# TeensySensor.net
KiCad netlist of a schematic drawn in EasyEDA Pro
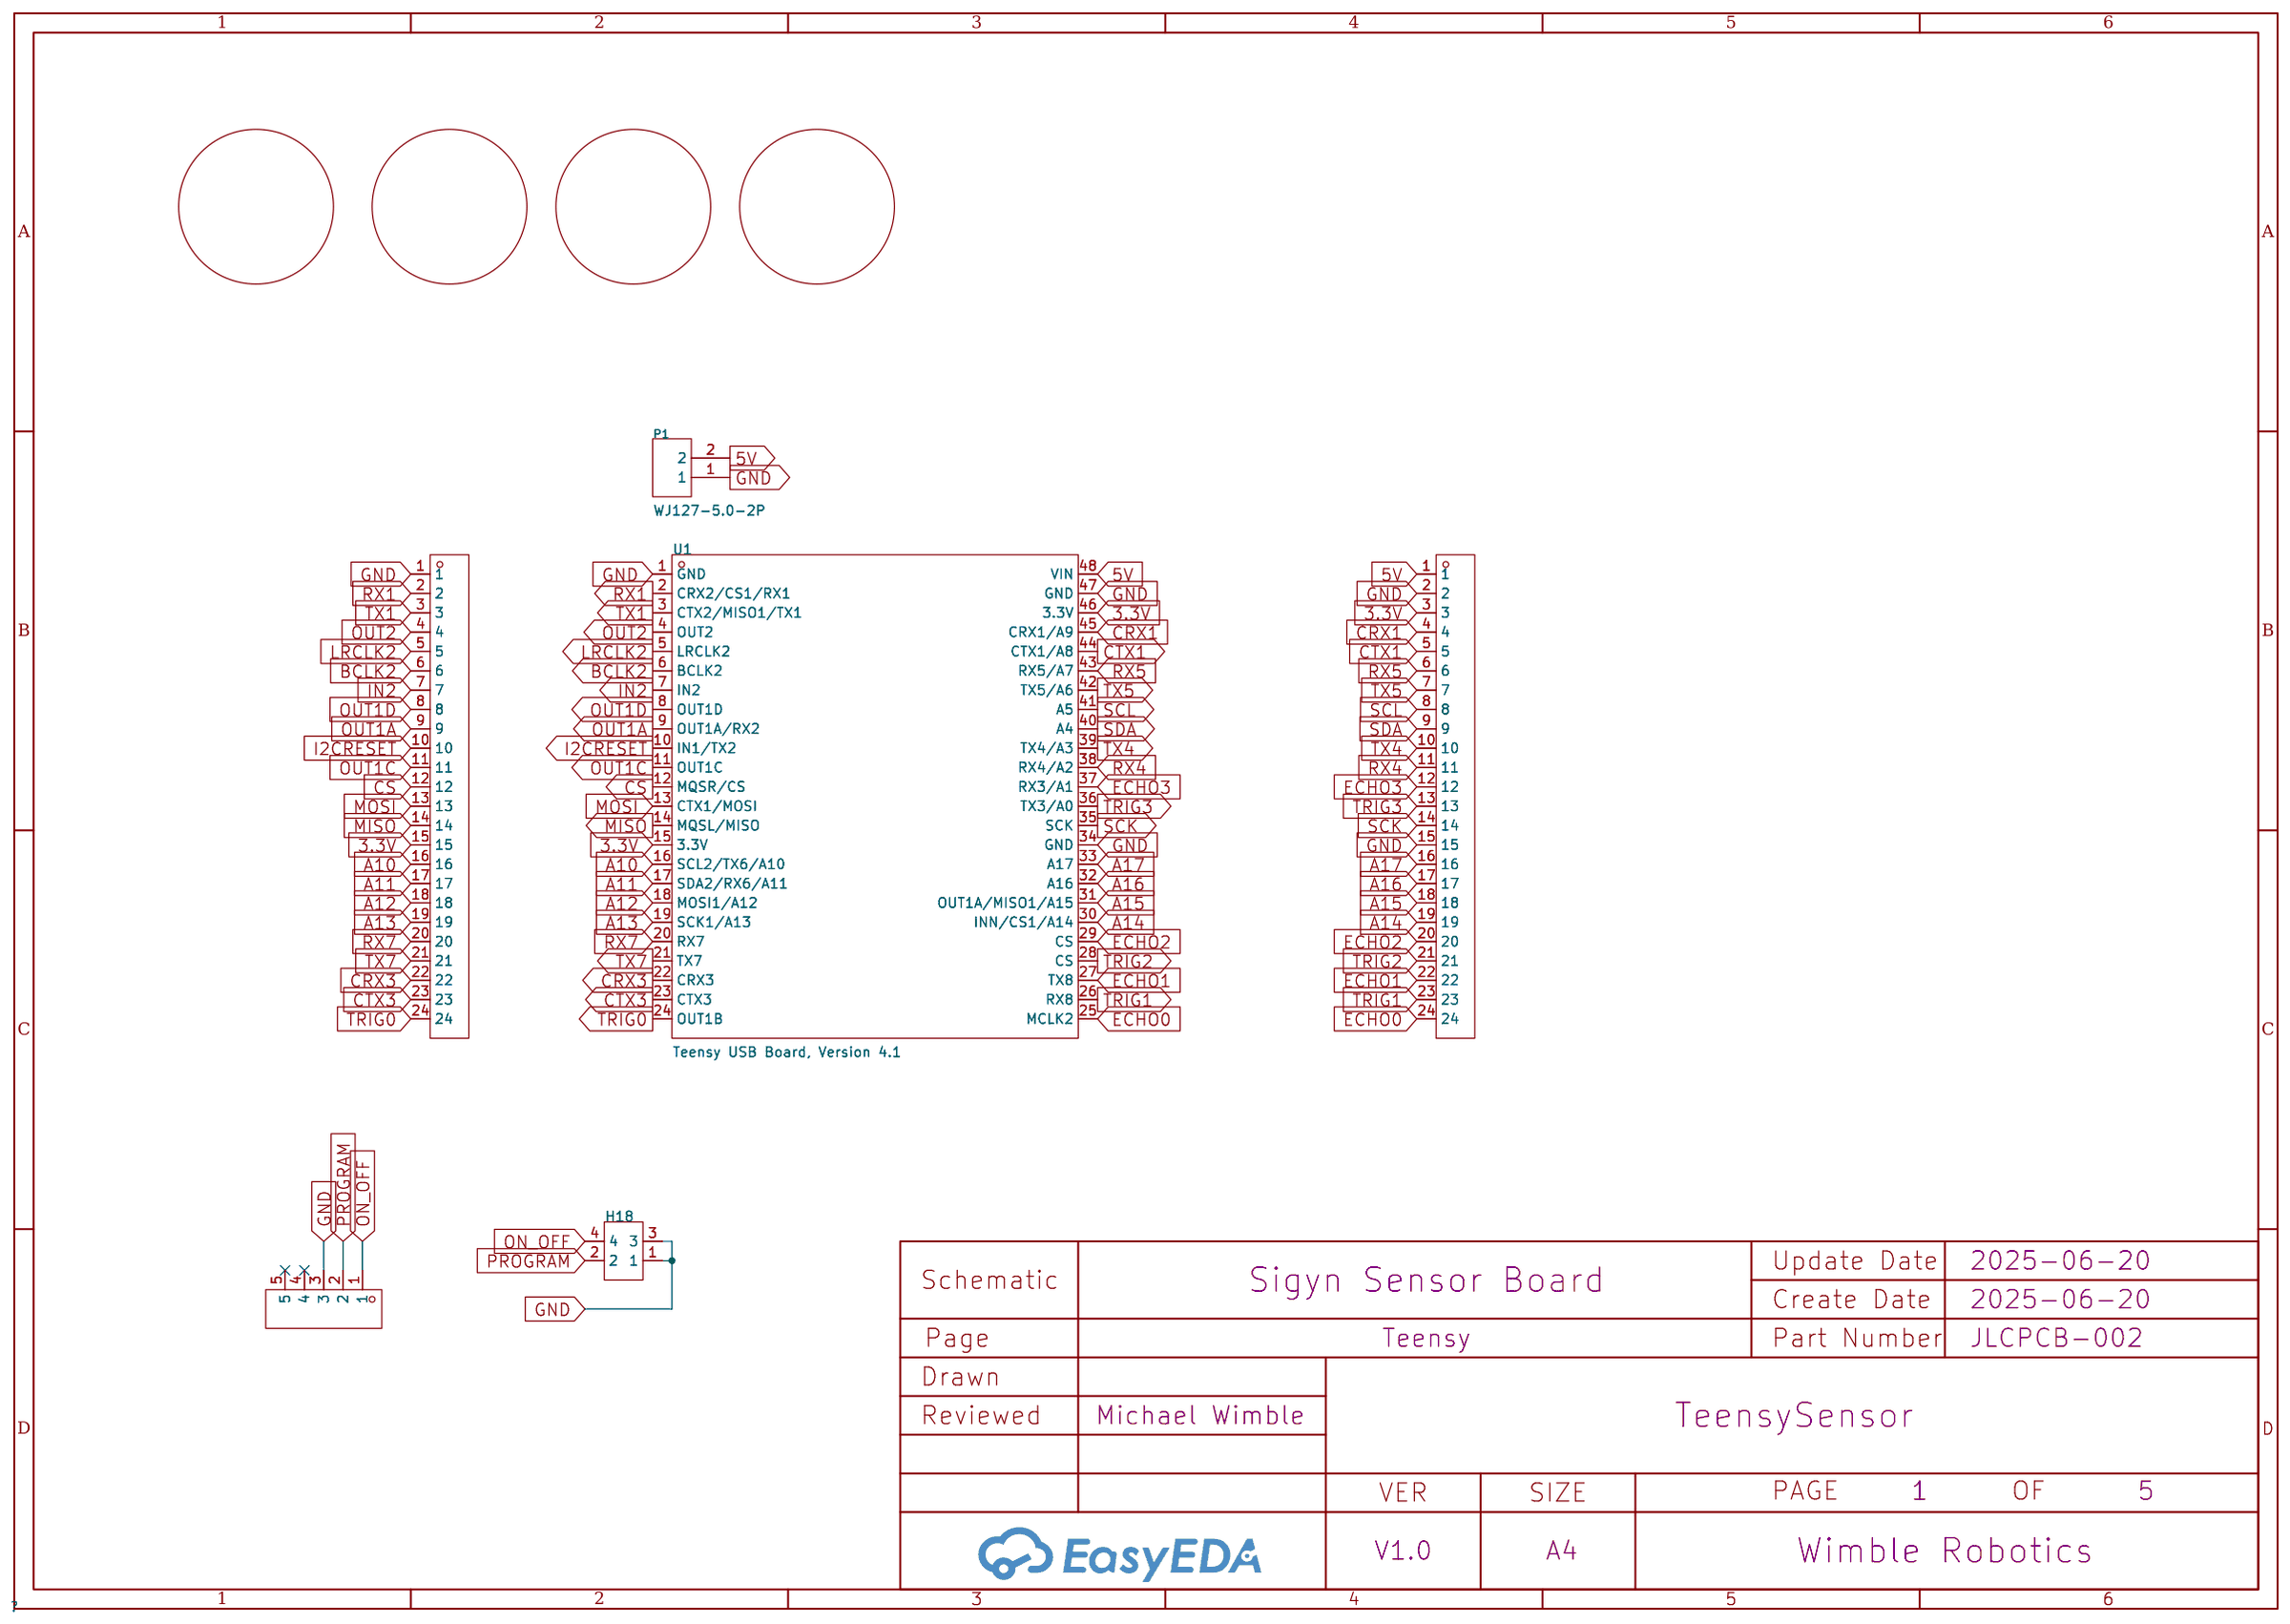
[diagram p0: Teensy]
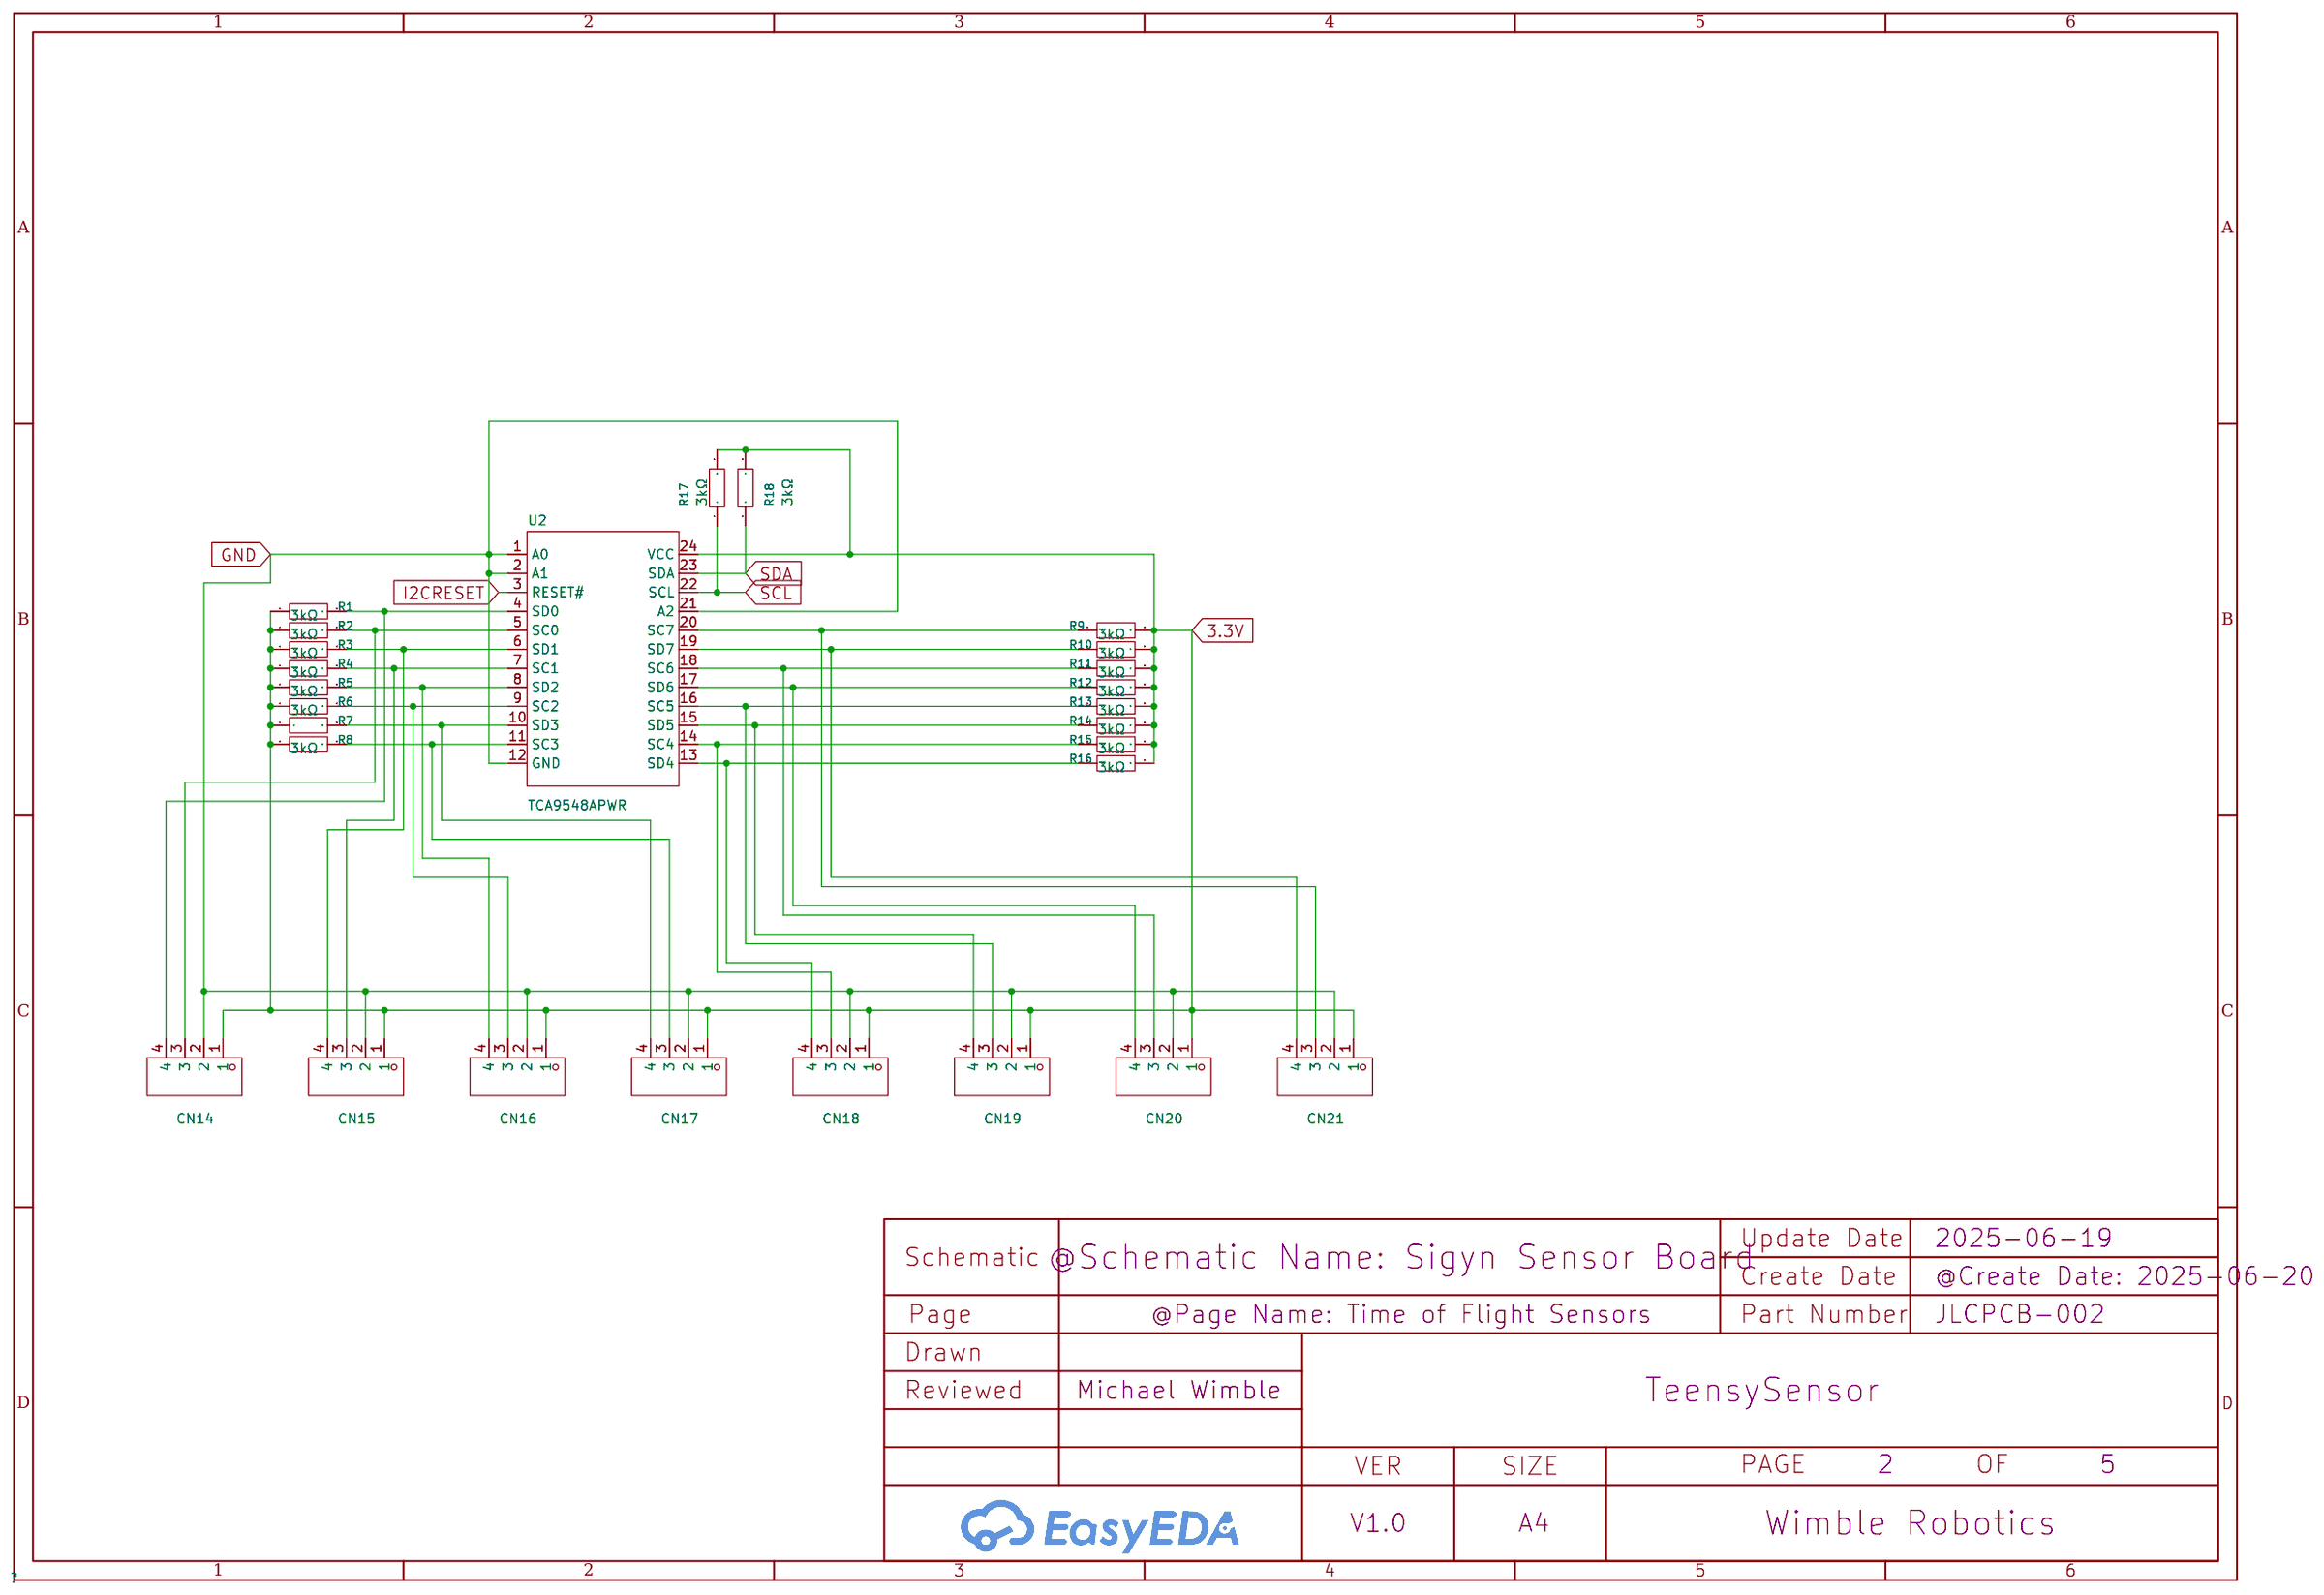
[diagram p1: Time of Flight Sensors]
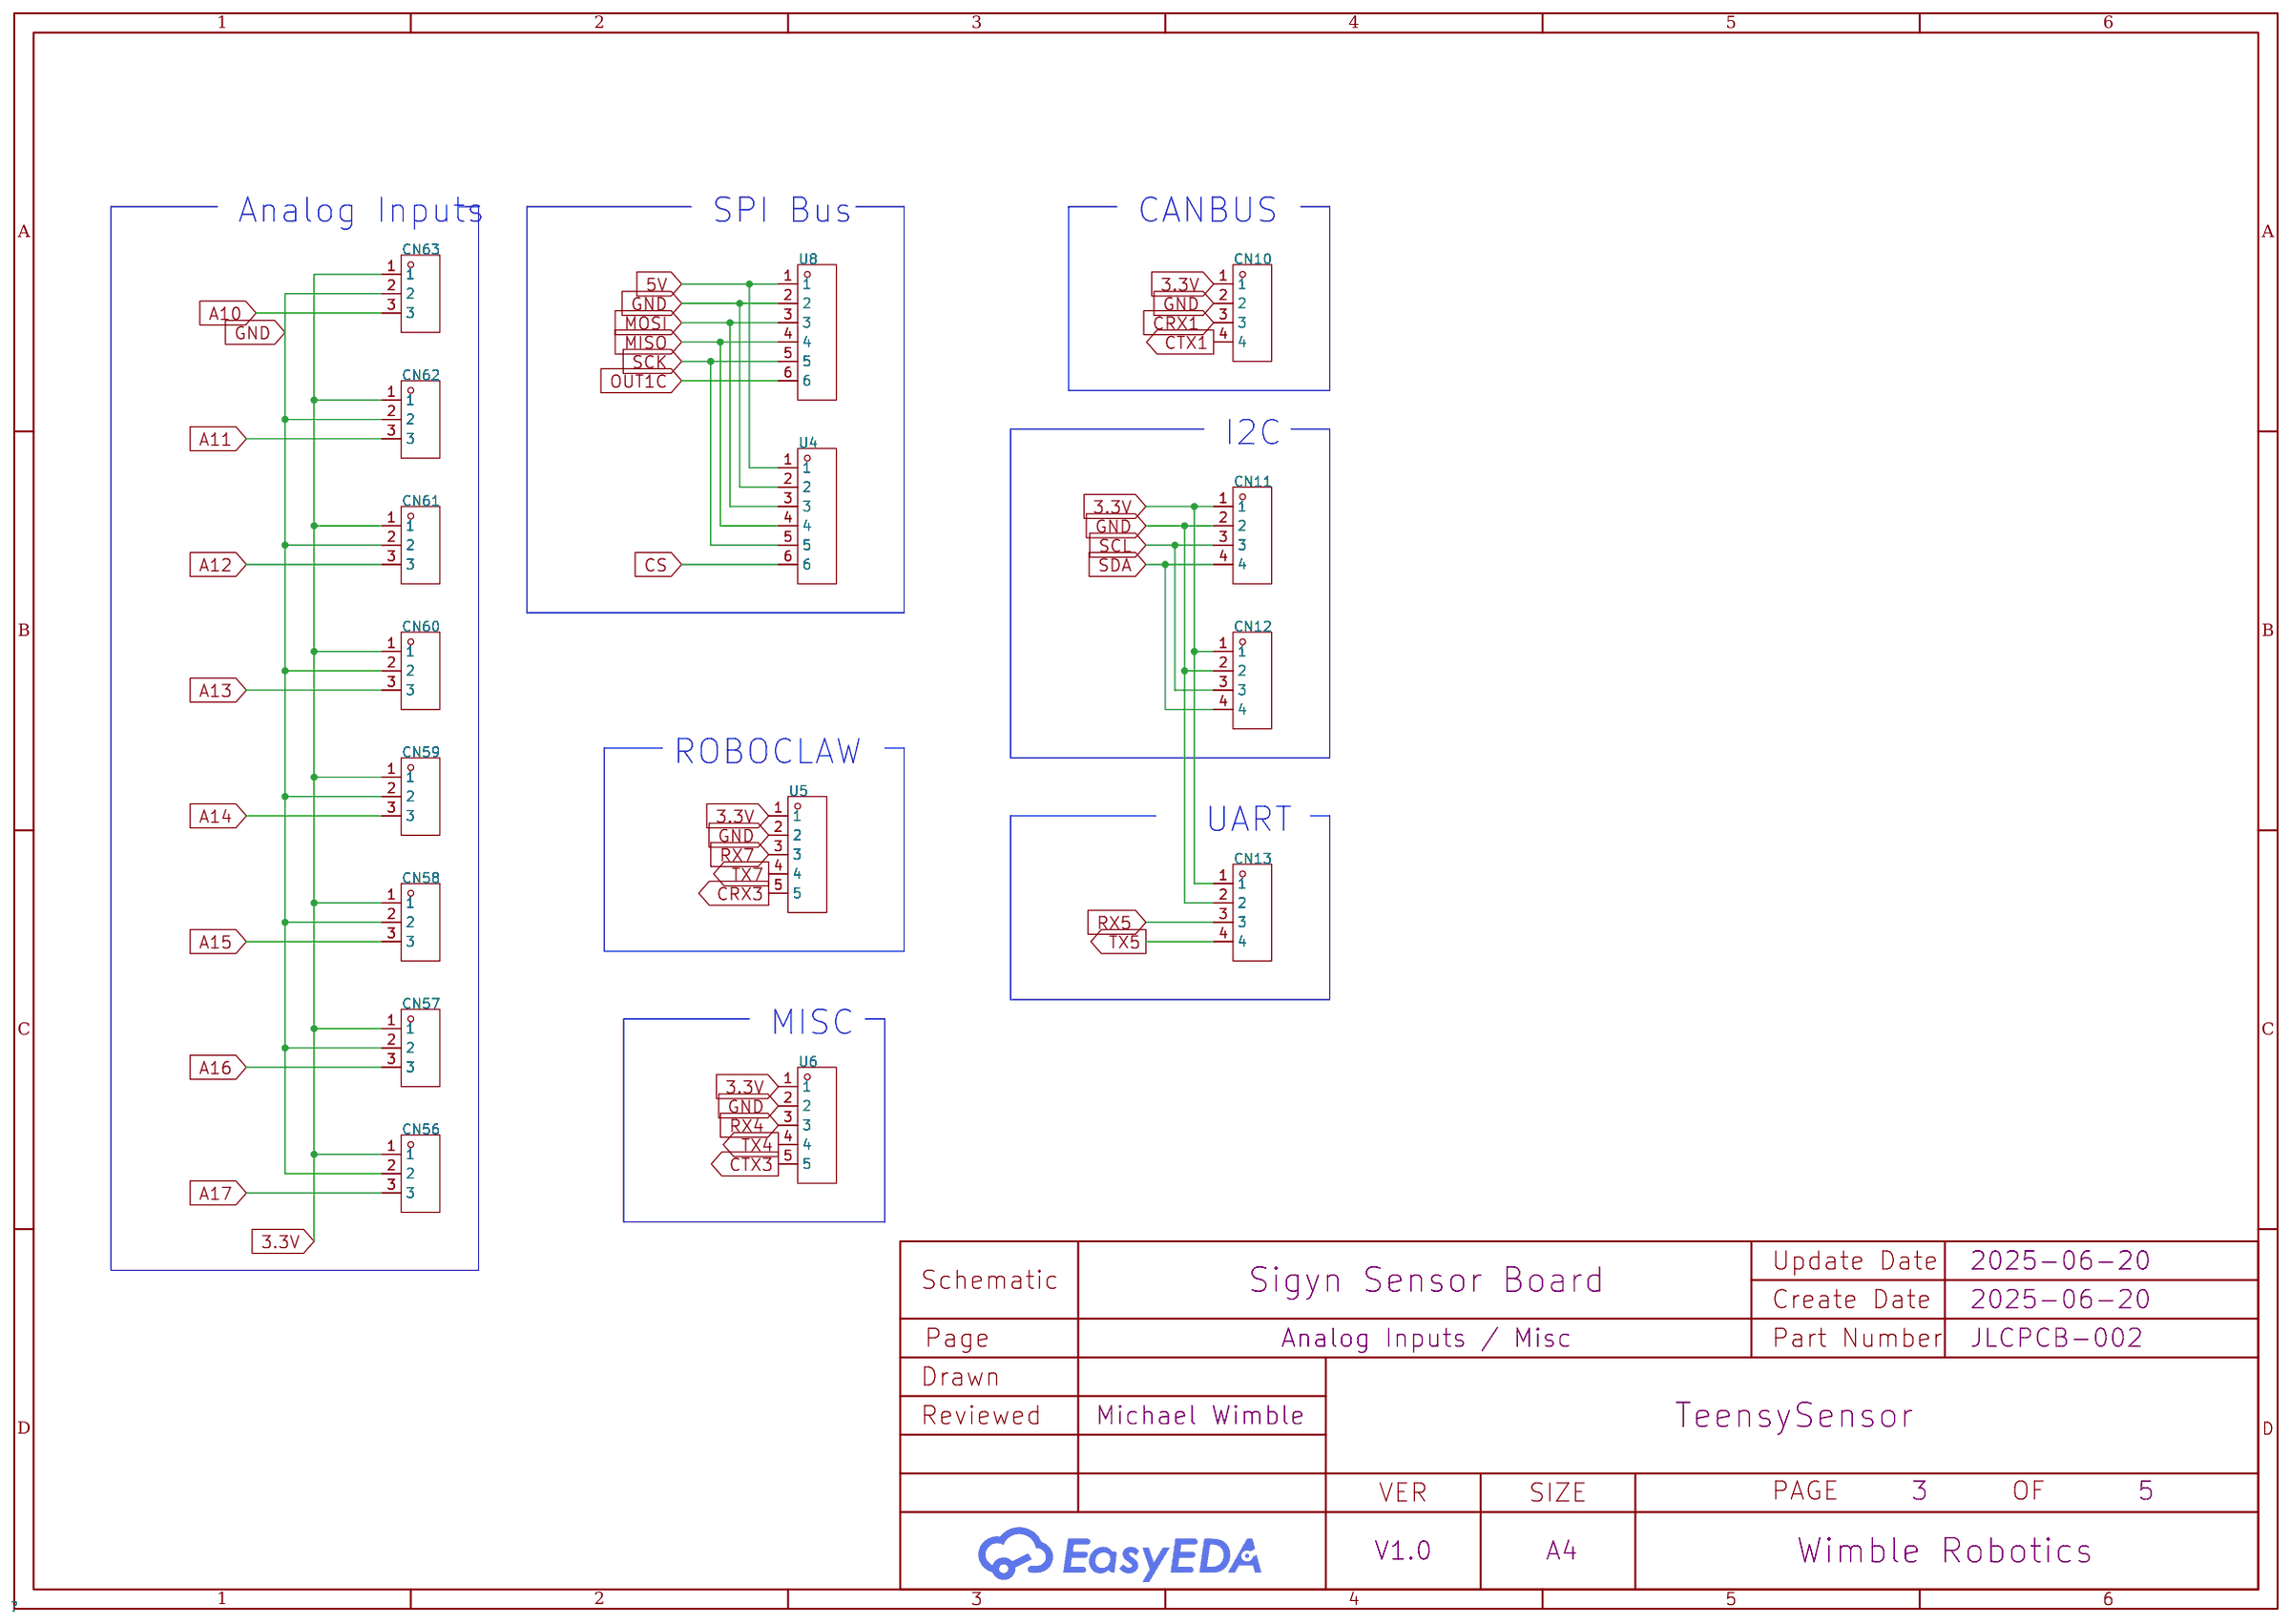
[diagram p2: Analog Inputs / Misc]
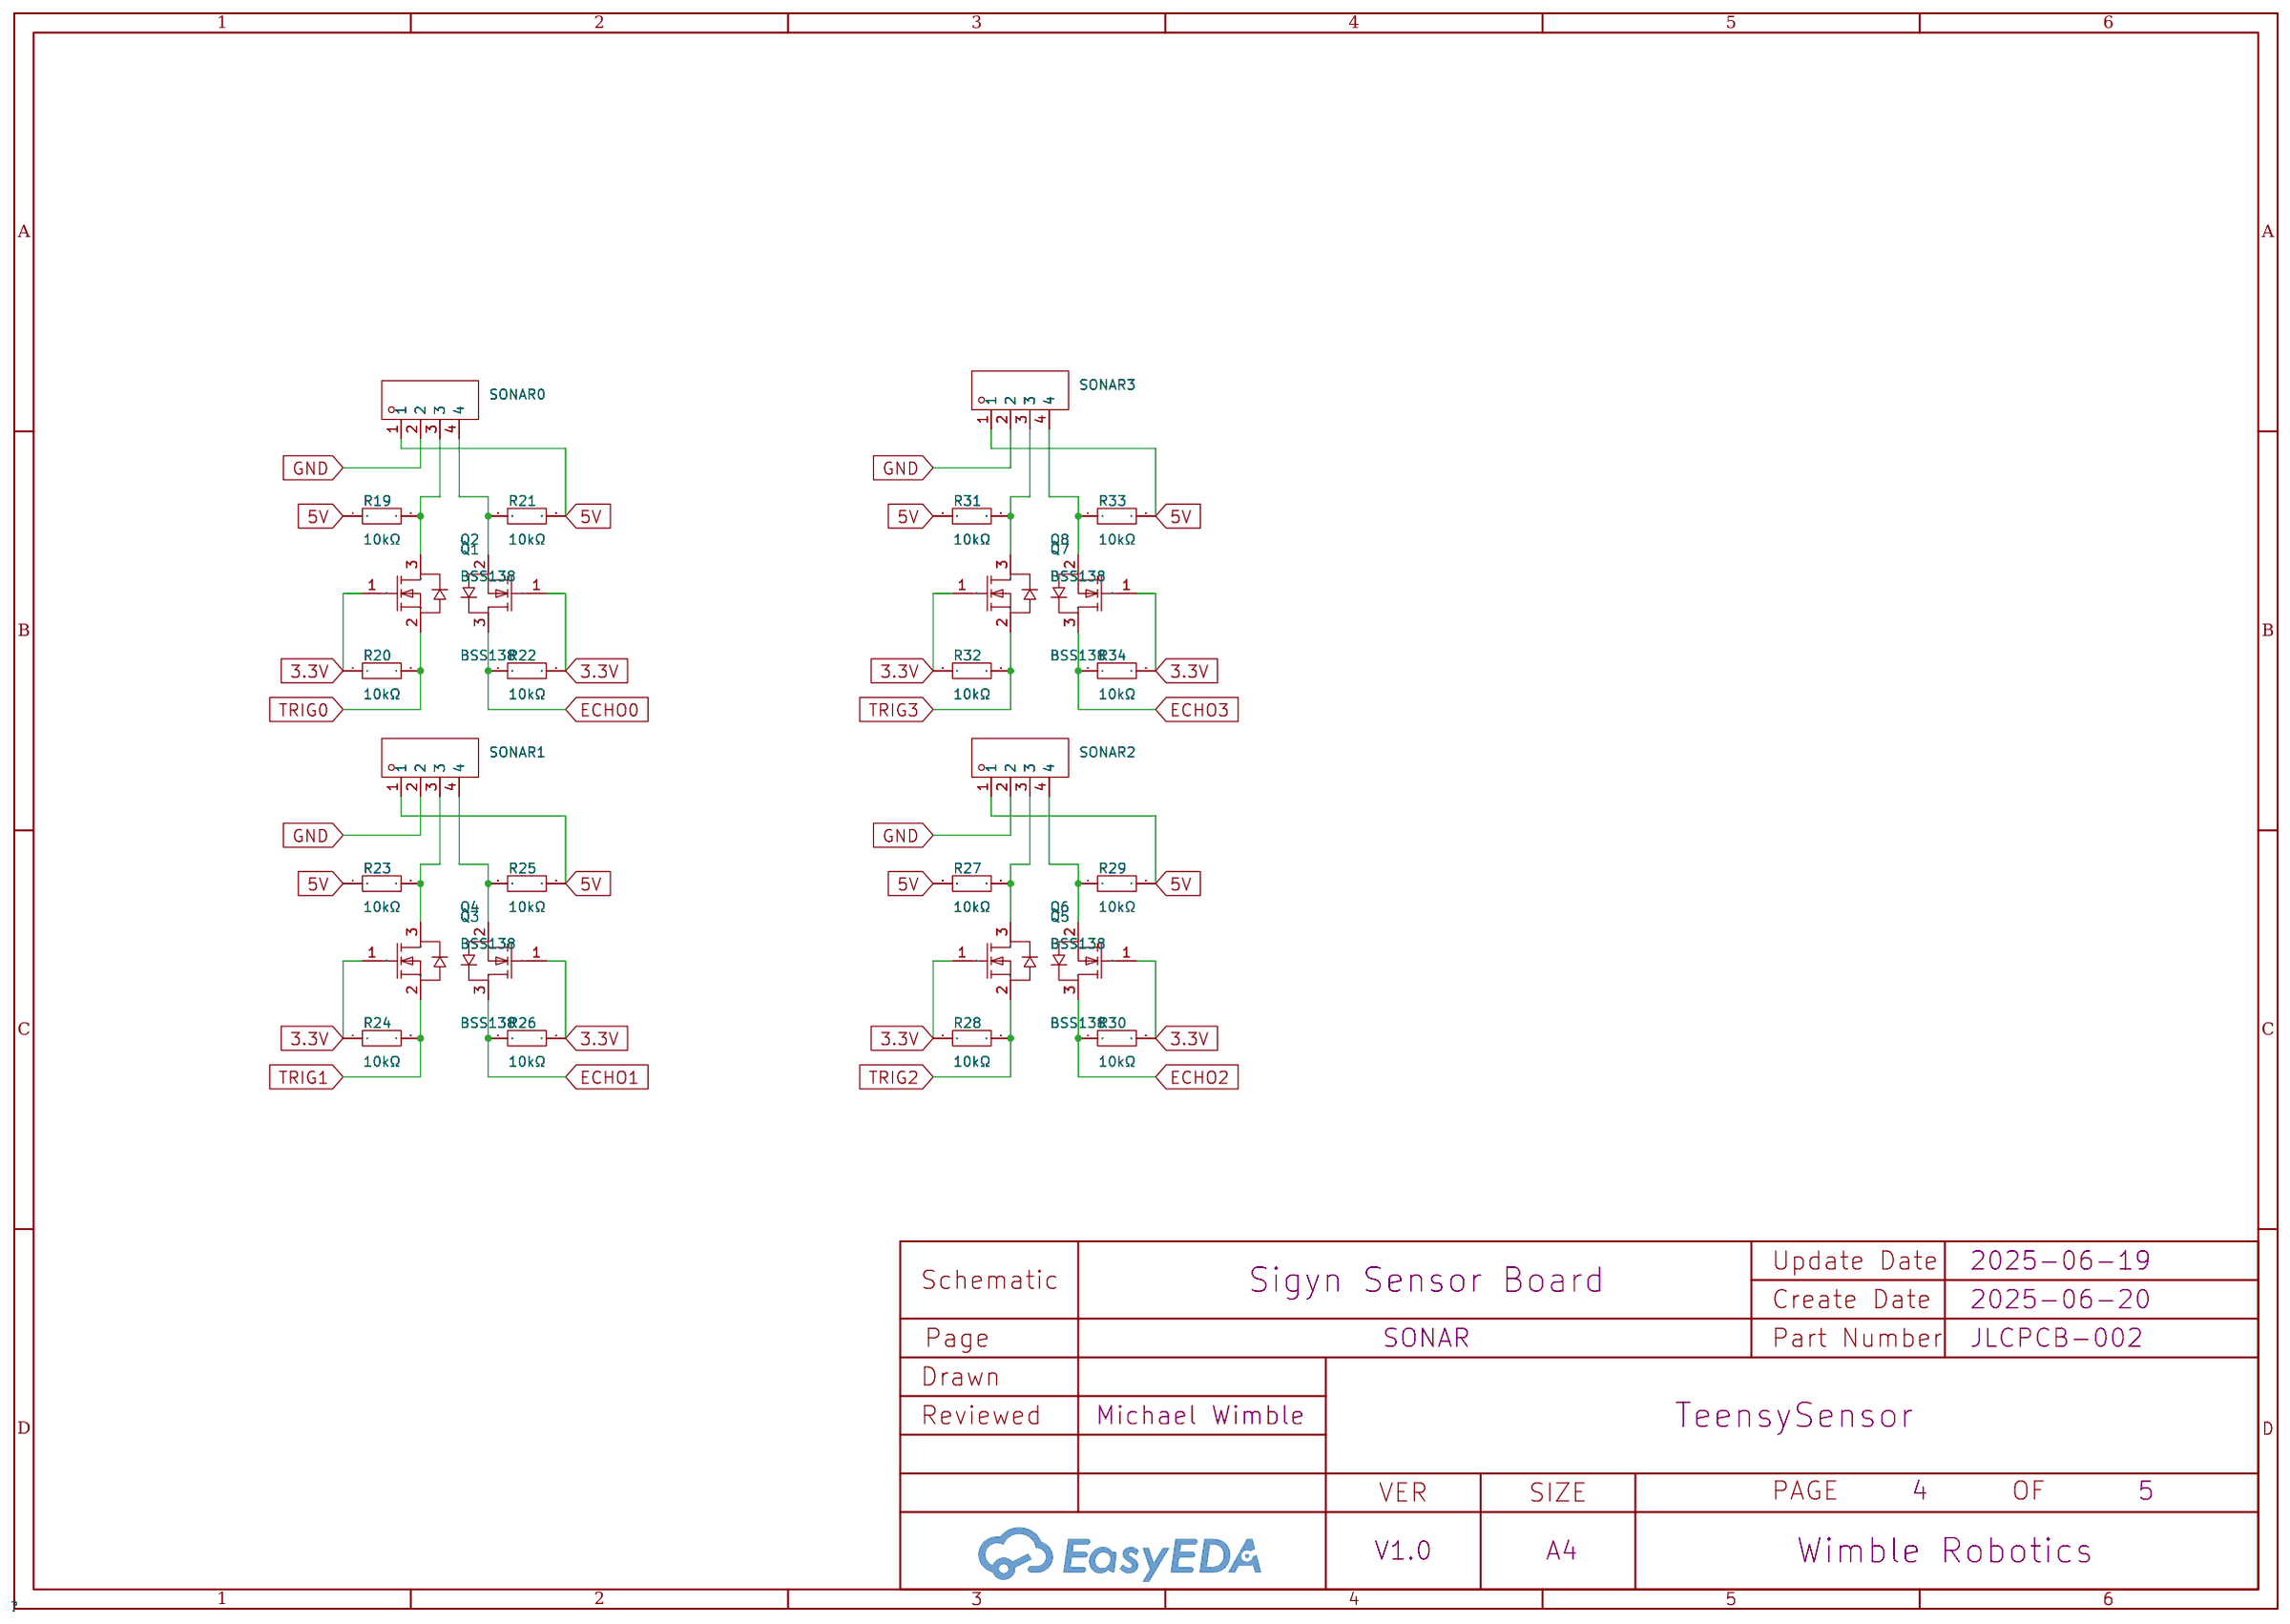
[diagram p3: SONAR]
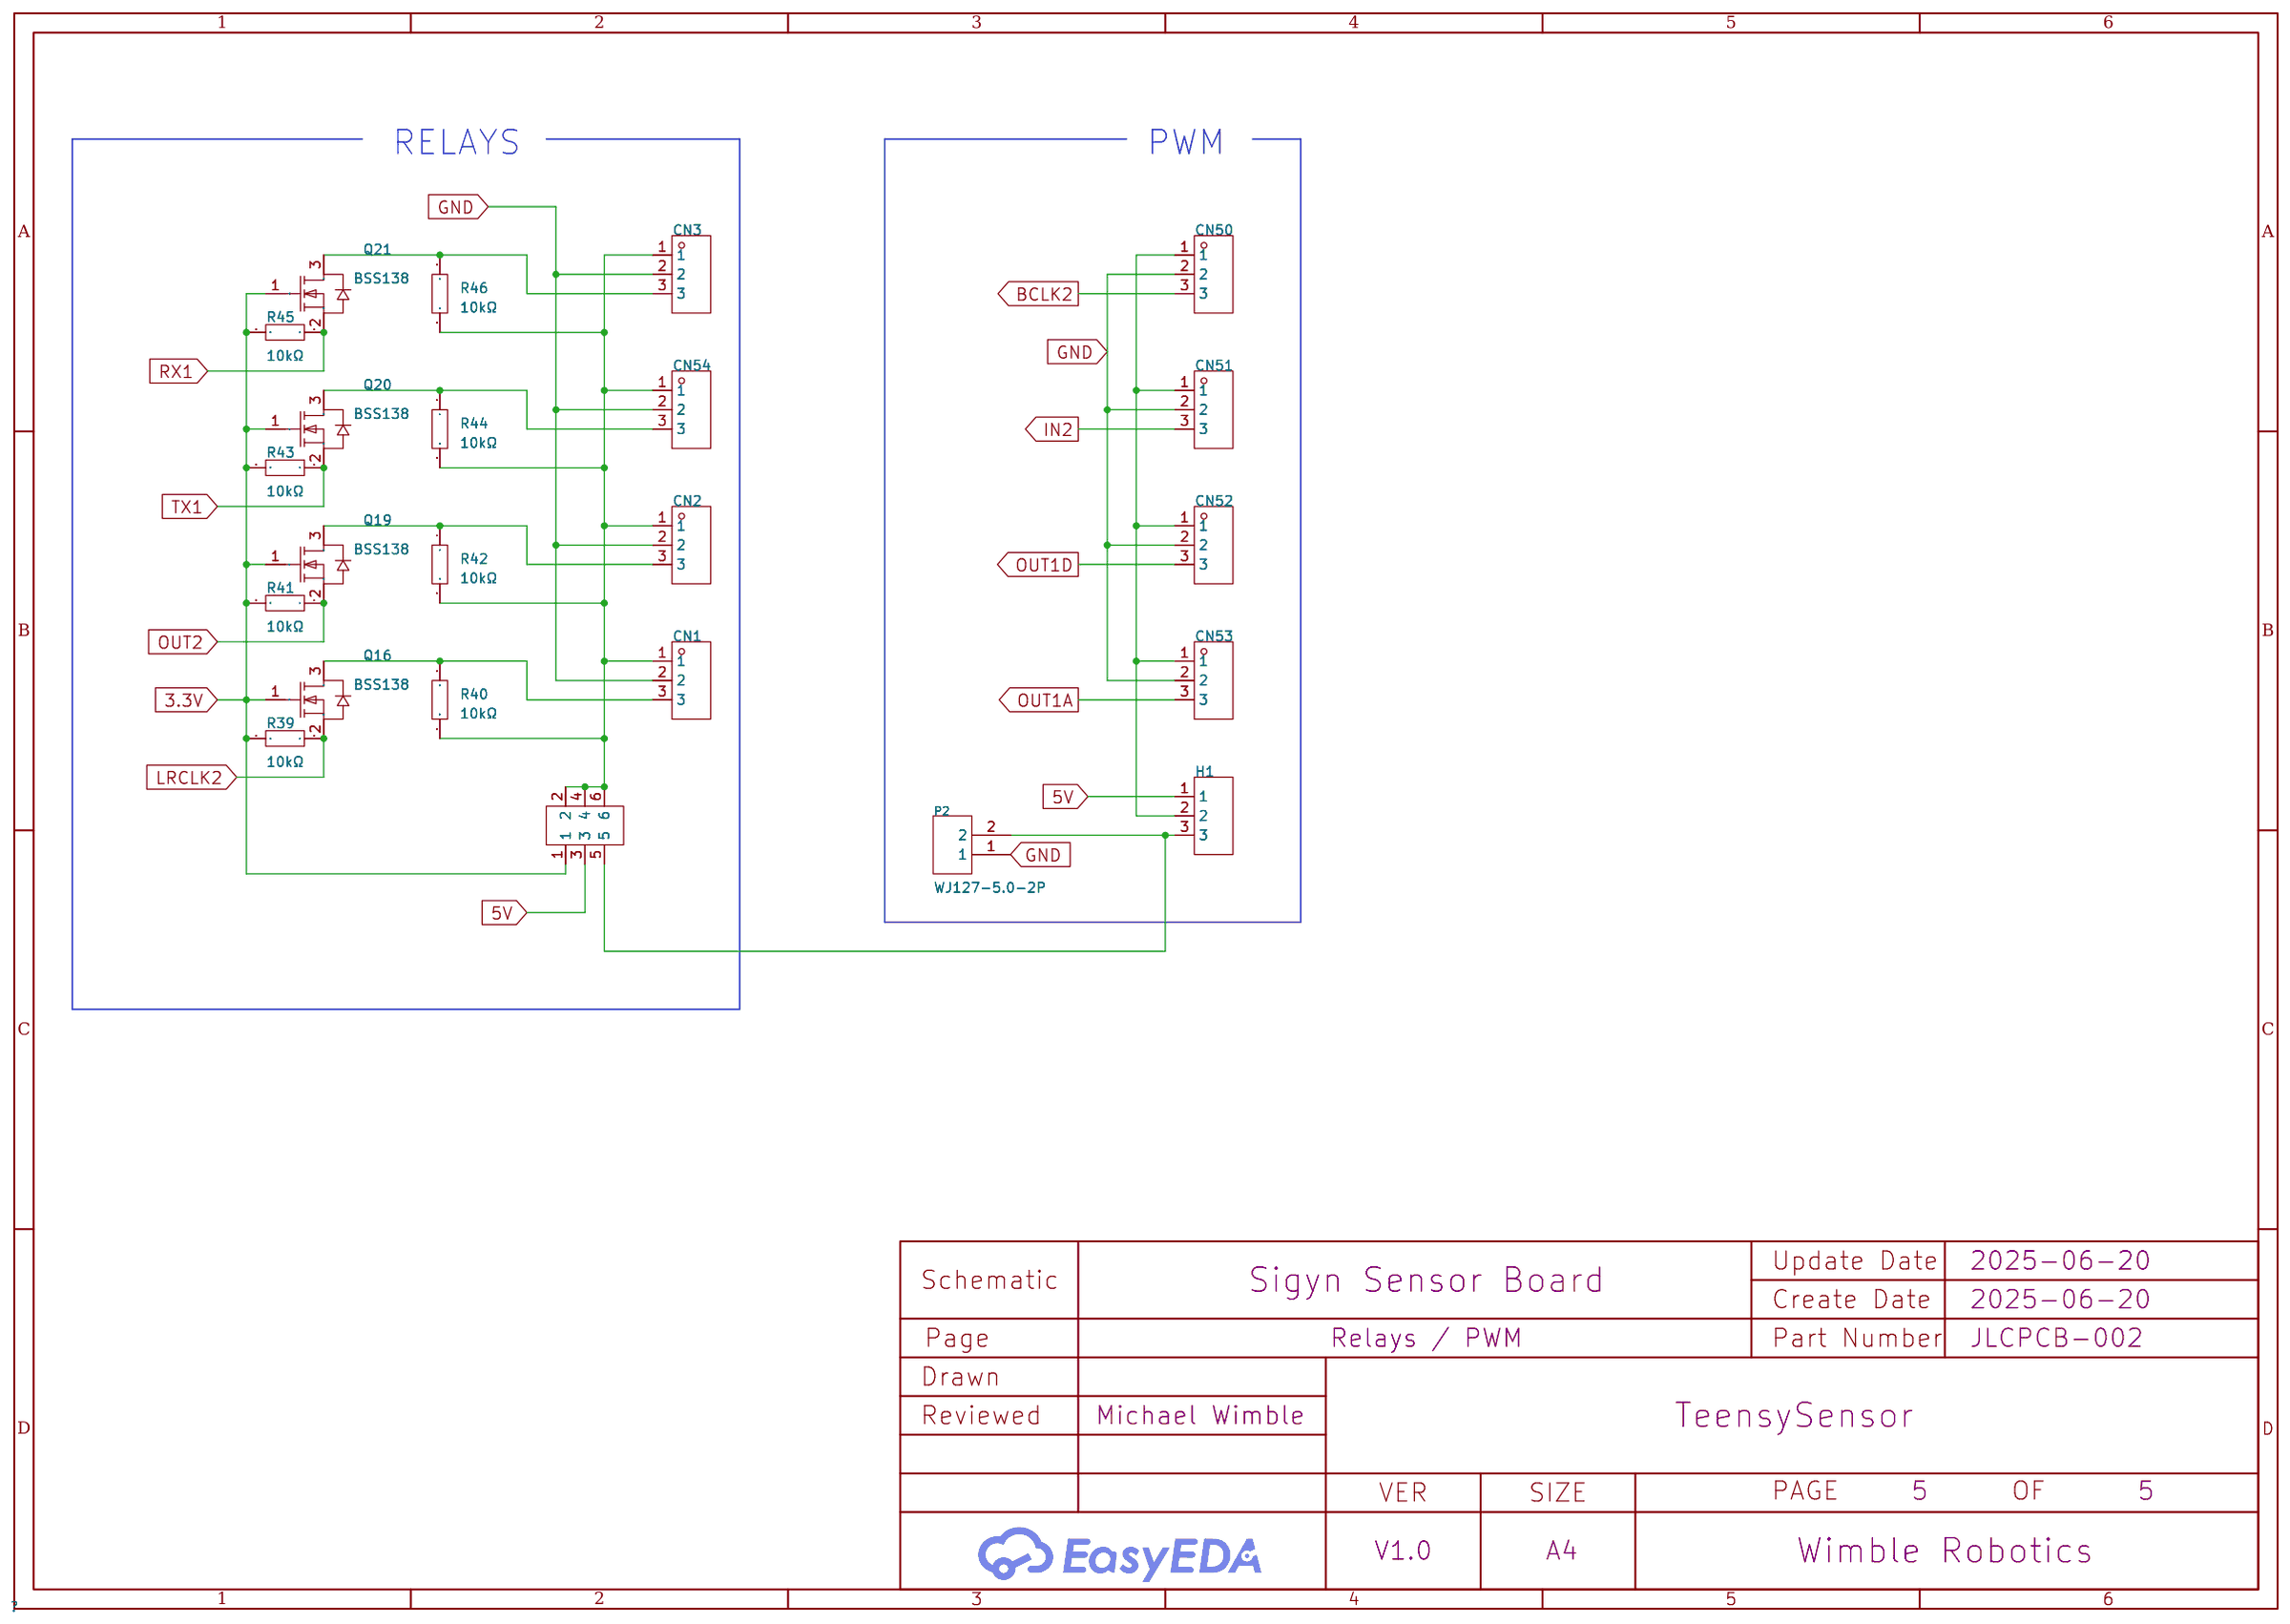
[diagram p4: Relays / PWM]

(export (version "E")
  (design (tool "Eeschema 10.0.6"))
  (components
    (comp (ref "H18")
      (value "HX PZ2.54-2x2P ZZ")
      (footprint "easyedapro:HDR-TH_HX-PZ2.54-2X2P-ZZ")
      (fields (field (name "Manufacturer") "hanxia(韩下)"))
      (libsource (lib "easyedapro") (part "HX PZ2.54-2X2P ZZ"))
    )
    (comp (ref "P1")
      (value "WJ127-5.0-2P")
      (footprint "easyedapro:CONN-TH_2P-P5.00_CPC3703CTR")
      (fields (field (name "Manufacturer") "KANGNEX(康奈克斯电气)"))
      (libsource (lib "easyedapro") (part "WJ127-5.0-2P"))
    )
    (comp (ref "U1")
      (value "Teensy USB Board, Version 4.1")
      (footprint "easyedapro:COMM-TH_L61.0-W17.8-P2.54")
      (libsource (lib "easyedapro") (part "TEENSY USB BOARD, VERSION 4.1"))
    )
    (comp (ref "U12")
      (value "~")
      (footprint "easyedapro:3.5mm_Hole")
      (description "Mounting hole")
      (libsource (lib "easyedapro") (part "3.5MMHole"))
    )
    (comp (ref "U13")
      (value "~")
      (footprint "easyedapro:3.5mm_Hole")
      (description "Mounting hole")
      (libsource (lib "easyedapro") (part "3.5MMHole"))
    )
    (comp (ref "U14")
      (value "~")
      (footprint "easyedapro:3.5mm_Hole")
      (description "Mounting hole")
      (libsource (lib "easyedapro") (part "3.5MMHole"))
    )
    (comp (ref "U15")
      (value "~")
      (footprint "easyedapro:3.5mm_Hole")
      (description "Mounting hole")
      (libsource (lib "easyedapro") (part "3.5MMHole"))
    )
    (comp (ref "U43")
      (value "HC-PM254-8.5H-1x24PZ")
      (footprint "easyedapro:HDR-TH_24P-P2.54-V-F")
      (fields (field (name "Manufacturer") "HC(虹成电子)"))
      (libsource (lib "easyedapro") (part "HC-PM254-8.5H-1X24PZ"))
    )
    (comp (ref "U44")
      (value "HC-PM254-8.5H-1x24PZ")
      (footprint "easyedapro:HDR-TH_24P-P2.54-V-F")
      (fields (field (name "Manufacturer") "HC(虹成电子)"))
      (libsource (lib "easyedapro") (part "HC-PM254-8.5H-1X24PZ"))
    )
    (comp (ref "U48")
      (value "PM2.54-1*5")
      (footprint "easyedapro:HDR-TH_5P-P2.54-V-F")
      (fields (field (name "Manufacturer") "ZHOURI(洲日)"))
      (libsource (lib "easyedapro") (part "PM2.54-1*5"))
    )
    (comp (ref "CN14")
      (value "ZX-XH2.54-4PZZ")
      (footprint "easyedapro:CONN-TH_4P-P2.50_4PIN")
      (fields (field (name "Manufacturer") "Megastar(兆星)"))
      (libsource (lib "easyedapro") (part "ZX-XH2.54-4PZZ"))
    )
    (comp (ref "CN15")
      (value "ZX-XH2.54-4PZZ")
      (footprint "easyedapro:CONN-TH_4P-P2.50_4PIN")
      (fields (field (name "Manufacturer") "Megastar(兆星)"))
      (libsource (lib "easyedapro") (part "ZX-XH2.54-4PZZ"))
    )
    (comp (ref "CN16")
      (value "ZX-XH2.54-4PZZ")
      (footprint "easyedapro:CONN-TH_4P-P2.50_4PIN")
      (fields (field (name "Manufacturer") "Megastar(兆星)"))
      (libsource (lib "easyedapro") (part "ZX-XH2.54-4PZZ"))
    )
    (comp (ref "CN17")
      (value "ZX-XH2.54-4PZZ")
      (footprint "easyedapro:CONN-TH_4P-P2.50_4PIN")
      (fields (field (name "Manufacturer") "Megastar(兆星)"))
      (libsource (lib "easyedapro") (part "ZX-XH2.54-4PZZ"))
    )
    (comp (ref "CN18")
      (value "ZX-XH2.54-4PZZ")
      (footprint "easyedapro:CONN-TH_4P-P2.50_4PIN")
      (fields (field (name "Manufacturer") "Megastar(兆星)"))
      (libsource (lib "easyedapro") (part "ZX-XH2.54-4PZZ"))
    )
    (comp (ref "CN19")
      (value "ZX-XH2.54-4PZZ")
      (footprint "easyedapro:CONN-TH_4P-P2.50_4PIN")
      (fields (field (name "Manufacturer") "Megastar(兆星)"))
      (libsource (lib "easyedapro") (part "ZX-XH2.54-4PZZ"))
    )
    (comp (ref "CN20")
      (value "ZX-XH2.54-4PZZ")
      (footprint "easyedapro:CONN-TH_4P-P2.50_4PIN")
      (fields (field (name "Manufacturer") "Megastar(兆星)"))
      (libsource (lib "easyedapro") (part "ZX-XH2.54-4PZZ"))
    )
    (comp (ref "CN21")
      (value "ZX-XH2.54-4PZZ")
      (footprint "easyedapro:CONN-TH_4P-P2.50_4PIN")
      (fields (field (name "Manufacturer") "Megastar(兆星)"))
      (libsource (lib "easyedapro") (part "ZX-XH2.54-4PZZ"))
    )
    (comp (ref "R1")
      (value "3kΩ")
      (footprint "easyedapro:R0603")
      (fields
        (field (name "Manufacturer Part") "0603WAF3001T5E")
        (field (name "Manufacturer") "UNI-ROYAL(厚声)")
      )
      (libsource (lib "easyedapro") (part "0603WAF3001T5E"))
    )
    (comp (ref "R2")
      (value "3kΩ")
      (footprint "easyedapro:R0603")
      (fields
        (field (name "Manufacturer Part") "0603WAF3001T5E")
        (field (name "Manufacturer") "UNI-ROYAL(厚声)")
      )
      (libsource (lib "easyedapro") (part "0603WAF3001T5E"))
    )
    (comp (ref "R3")
      (value "3kΩ")
      (footprint "easyedapro:R0603")
      (fields
        (field (name "Manufacturer Part") "0603WAF3001T5E")
        (field (name "Manufacturer") "UNI-ROYAL(厚声)")
      )
      (libsource (lib "easyedapro") (part "0603WAF3001T5E"))
    )
    (comp (ref "R4")
      (value "3kΩ")
      (footprint "easyedapro:R0603")
      (fields
        (field (name "Manufacturer Part") "0603WAF3001T5E")
        (field (name "Manufacturer") "UNI-ROYAL(厚声)")
      )
      (libsource (lib "easyedapro") (part "0603WAF3001T5E"))
    )
    (comp (ref "R5")
      (value "3kΩ")
      (footprint "easyedapro:R0603")
      (fields
        (field (name "Manufacturer Part") "0603WAF3001T5E")
        (field (name "Manufacturer") "UNI-ROYAL(厚声)")
      )
      (libsource (lib "easyedapro") (part "0603WAF3001T5E"))
    )
    (comp (ref "R6")
      (value "3kΩ")
      (footprint "easyedapro:R0603")
      (fields
        (field (name "Manufacturer Part") "0603WAF3001T5E")
        (field (name "Manufacturer") "UNI-ROYAL(厚声)")
      )
      (libsource (lib "easyedapro") (part "0603WAF3001T5E"))
    )
    (comp (ref "R7")
      (value "3kΩ")
      (footprint "easyedapro:R0603")
      (fields
        (field (name "Manufacturer Part") "0603WAF3001T5E")
        (field (name "Manufacturer") "UNI-ROYAL(厚声)")
      )
      (libsource (lib "easyedapro") (part "0603WAF3001T5E"))
    )
    (comp (ref "R8")
      (value "3kΩ")
      (footprint "easyedapro:R0603")
      (fields
        (field (name "Manufacturer Part") "0603WAF3001T5E")
        (field (name "Manufacturer") "UNI-ROYAL(厚声)")
      )
      (libsource (lib "easyedapro") (part "0603WAF3001T5E"))
    )
    (comp (ref "R9")
      (value "3kΩ")
      (footprint "easyedapro:R0603")
      (fields
        (field (name "Manufacturer Part") "0603WAF3001T5E")
        (field (name "Manufacturer") "UNI-ROYAL(厚声)")
      )
      (libsource (lib "easyedapro") (part "0603WAF3001T5E"))
    )
    (comp (ref "R10")
      (value "3kΩ")
      (footprint "easyedapro:R0603")
      (fields
        (field (name "Manufacturer Part") "0603WAF3001T5E")
        (field (name "Manufacturer") "UNI-ROYAL(厚声)")
      )
      (libsource (lib "easyedapro") (part "0603WAF3001T5E"))
    )
    (comp (ref "R11")
      (value "3kΩ")
      (footprint "easyedapro:R0603")
      (fields
        (field (name "Manufacturer Part") "0603WAF3001T5E")
        (field (name "Manufacturer") "UNI-ROYAL(厚声)")
      )
      (libsource (lib "easyedapro") (part "0603WAF3001T5E"))
    )
    (comp (ref "R12")
      (value "3kΩ")
      (footprint "easyedapro:R0603")
      (fields
        (field (name "Manufacturer Part") "0603WAF3001T5E")
        (field (name "Manufacturer") "UNI-ROYAL(厚声)")
      )
      (libsource (lib "easyedapro") (part "0603WAF3001T5E"))
    )
    (comp (ref "R13")
      (value "3kΩ")
      (footprint "easyedapro:R0603")
      (fields
        (field (name "Manufacturer Part") "0603WAF3001T5E")
        (field (name "Manufacturer") "UNI-ROYAL(厚声)")
      )
      (libsource (lib "easyedapro") (part "0603WAF3001T5E"))
    )
    (comp (ref "R14")
      (value "3kΩ")
      (footprint "easyedapro:R0603")
      (fields
        (field (name "Manufacturer Part") "0603WAF3001T5E")
        (field (name "Manufacturer") "UNI-ROYAL(厚声)")
      )
      (libsource (lib "easyedapro") (part "0603WAF3001T5E"))
    )
    (comp (ref "R15")
      (value "3kΩ")
      (footprint "easyedapro:R0603")
      (fields
        (field (name "Manufacturer Part") "0603WAF3001T5E")
        (field (name "Manufacturer") "UNI-ROYAL(厚声)")
      )
      (libsource (lib "easyedapro") (part "0603WAF3001T5E"))
    )
    (comp (ref "R16")
      (value "3kΩ")
      (footprint "easyedapro:R0603")
      (fields
        (field (name "Manufacturer Part") "0603WAF3001T5E")
        (field (name "Manufacturer") "UNI-ROYAL(厚声)")
      )
      (libsource (lib "easyedapro") (part "0603WAF3001T5E"))
    )
    (comp (ref "R17")
      (value "3kΩ")
      (footprint "easyedapro:R0603")
      (fields
        (field (name "Manufacturer Part") "0603WAF3001T5E")
        (field (name "Manufacturer") "UNI-ROYAL(厚声)")
      )
      (libsource (lib "easyedapro") (part "0603WAF3001T5E"))
    )
    (comp (ref "R18")
      (value "3kΩ")
      (footprint "easyedapro:R0603")
      (fields
        (field (name "Manufacturer Part") "0603WAF3001T5E")
        (field (name "Manufacturer") "UNI-ROYAL(厚声)")
      )
      (libsource (lib "easyedapro") (part "0603WAF3001T5E"))
    )
    (comp (ref "U2")
      (value "TCA9548APWR")
      (footprint "easyedapro:TSSOP-24_L7.8-W4.4-P0.65-LS6.4-BL")
      (fields (field (name "Manufacturer") "TI(德州仪器)"))
      (libsource (lib "easyedapro") (part "TCA9548APWR"))
    )
    (comp (ref "CN10")
      (value "ZX-XH2.54-4PZZ")
      (footprint "easyedapro:CONN-TH_4P-P2.50_4PIN")
      (fields (field (name "Manufacturer") "Megastar(兆星)"))
      (libsource (lib "easyedapro") (part "ZX-XH2.54-4PZZ"))
    )
    (comp (ref "CN11")
      (value "ZX-XH2.54-4PZZ")
      (footprint "easyedapro:CONN-TH_4P-P2.50_4PIN")
      (fields (field (name "Manufacturer") "Megastar(兆星)"))
      (libsource (lib "easyedapro") (part "ZX-XH2.54-4PZZ"))
    )
    (comp (ref "CN12")
      (value "ZX-XH2.54-4PZZ")
      (footprint "easyedapro:CONN-TH_4P-P2.50_4PIN")
      (fields (field (name "Manufacturer") "Megastar(兆星)"))
      (libsource (lib "easyedapro") (part "ZX-XH2.54-4PZZ"))
    )
    (comp (ref "CN13")
      (value "ZX-XH2.54-4PZZ")
      (footprint "easyedapro:CONN-TH_4P-P2.50_4PIN")
      (fields (field (name "Manufacturer") "Megastar(兆星)"))
      (libsource (lib "easyedapro") (part "ZX-XH2.54-4PZZ"))
    )
    (comp (ref "CN56")
      (value "ZX-XH2.54-3PZZ")
      (footprint "easyedapro:CONN-TH_3P-P2.54_2501S-3P")
      (fields (field (name "Manufacturer") "Megastar(兆星)"))
      (libsource (lib "easyedapro") (part "ZX-XH2.54-3PZZ"))
    )
    (comp (ref "CN57")
      (value "ZX-XH2.54-3PZZ")
      (footprint "easyedapro:CONN-TH_3P-P2.54_2501S-3P")
      (fields (field (name "Manufacturer") "Megastar(兆星)"))
      (libsource (lib "easyedapro") (part "ZX-XH2.54-3PZZ"))
    )
    (comp (ref "CN58")
      (value "ZX-XH2.54-3PZZ")
      (footprint "easyedapro:CONN-TH_3P-P2.54_2501S-3P")
      (fields (field (name "Manufacturer") "Megastar(兆星)"))
      (libsource (lib "easyedapro") (part "ZX-XH2.54-3PZZ"))
    )
    (comp (ref "CN59")
      (value "ZX-XH2.54-3PZZ")
      (footprint "easyedapro:CONN-TH_3P-P2.54_2501S-3P")
      (fields (field (name "Manufacturer") "Megastar(兆星)"))
      (libsource (lib "easyedapro") (part "ZX-XH2.54-3PZZ"))
    )
    (comp (ref "CN60")
      (value "ZX-XH2.54-3PZZ")
      (footprint "easyedapro:CONN-TH_3P-P2.54_2501S-3P")
      (fields (field (name "Manufacturer") "Megastar(兆星)"))
      (libsource (lib "easyedapro") (part "ZX-XH2.54-3PZZ"))
    )
    (comp (ref "CN61")
      (value "ZX-XH2.54-3PZZ")
      (footprint "easyedapro:CONN-TH_3P-P2.54_2501S-3P")
      (fields (field (name "Manufacturer") "Megastar(兆星)"))
      (libsource (lib "easyedapro") (part "ZX-XH2.54-3PZZ"))
    )
    (comp (ref "CN62")
      (value "ZX-XH2.54-3PZZ")
      (footprint "easyedapro:CONN-TH_3P-P2.54_2501S-3P")
      (fields (field (name "Manufacturer") "Megastar(兆星)"))
      (libsource (lib "easyedapro") (part "ZX-XH2.54-3PZZ"))
    )
    (comp (ref "CN63")
      (value "ZX-XH2.54-3PZZ")
      (footprint "easyedapro:CONN-TH_3P-P2.54_2501S-3P")
      (fields (field (name "Manufacturer") "Megastar(兆星)"))
      (libsource (lib "easyedapro") (part "ZX-XH2.54-3PZZ"))
    )
    (comp (ref "U4")
      (value "ZX-XH2.54-6PZZ")
      (footprint "easyedapro:CONN-TH_6P-P2.50_ZX-XH2.54-6PZZ")
      (fields (field (name "Manufacturer") "Megastar(兆星)"))
      (libsource (lib "easyedapro") (part "ZX-XH2.54-6PZZ"))
    )
    (comp (ref "U5")
      (value "ZX-XH2.54-5PZZ")
      (footprint "easyedapro:CONN-TH_5P-P2.50_ZX-XH2.54-5PZZ")
      (fields (field (name "Manufacturer") "Megastar(兆星)"))
      (libsource (lib "easyedapro") (part "ZX-XH2.54-5PZZ"))
    )
    (comp (ref "U6")
      (value "ZX-XH2.54-5PZZ")
      (footprint "easyedapro:CONN-TH_5P-P2.50_ZX-XH2.54-5PZZ")
      (fields (field (name "Manufacturer") "Megastar(兆星)"))
      (libsource (lib "easyedapro") (part "ZX-XH2.54-5PZZ"))
    )
    (comp (ref "U8")
      (value "ZX-XH2.54-6PZZ")
      (footprint "easyedapro:CONN-TH_6P-P2.50_ZX-XH2.54-6PZZ")
      (fields (field (name "Manufacturer") "Megastar(兆星)"))
      (libsource (lib "easyedapro") (part "ZX-XH2.54-6PZZ"))
    )
    (comp (ref "Q1")
      (value "BSS138")
      (footprint "easyedapro:SOT-23-3_L2.9-W1.6-P1.90-LS2.8-BR")
      (fields (field (name "Manufacturer") "TECH PUBLIC(台舟)"))
      (libsource (lib "easyedapro") (part "BSS138_C18212695"))
    )
    (comp (ref "Q2")
      (value "BSS138")
      (footprint "easyedapro:SOT-23-3_L2.9-W1.6-P1.90-LS2.8-BR")
      (fields (field (name "Manufacturer") "TECH PUBLIC(台舟)"))
      (libsource (lib "easyedapro") (part "BSS138_C18212695"))
    )
    (comp (ref "Q3")
      (value "BSS138")
      (footprint "easyedapro:SOT-23-3_L2.9-W1.6-P1.90-LS2.8-BR")
      (fields (field (name "Manufacturer") "TECH PUBLIC(台舟)"))
      (libsource (lib "easyedapro") (part "BSS138_C18212695"))
    )
    (comp (ref "Q4")
      (value "BSS138")
      (footprint "easyedapro:SOT-23-3_L2.9-W1.6-P1.90-LS2.8-BR")
      (fields (field (name "Manufacturer") "TECH PUBLIC(台舟)"))
      (libsource (lib "easyedapro") (part "BSS138_C18212695"))
    )
    (comp (ref "Q5")
      (value "BSS138")
      (footprint "easyedapro:SOT-23-3_L2.9-W1.6-P1.90-LS2.8-BR")
      (fields (field (name "Manufacturer") "TECH PUBLIC(台舟)"))
      (libsource (lib "easyedapro") (part "BSS138_C18212695"))
    )
    (comp (ref "Q6")
      (value "BSS138")
      (footprint "easyedapro:SOT-23-3_L2.9-W1.6-P1.90-LS2.8-BR")
      (fields (field (name "Manufacturer") "TECH PUBLIC(台舟)"))
      (libsource (lib "easyedapro") (part "BSS138_C18212695"))
    )
    (comp (ref "Q7")
      (value "BSS138")
      (footprint "easyedapro:SOT-23-3_L2.9-W1.6-P1.90-LS2.8-BR")
      (fields (field (name "Manufacturer") "TECH PUBLIC(台舟)"))
      (libsource (lib "easyedapro") (part "BSS138_C18212695"))
    )
    (comp (ref "Q8")
      (value "BSS138")
      (footprint "easyedapro:SOT-23-3_L2.9-W1.6-P1.90-LS2.8-BR")
      (fields (field (name "Manufacturer") "TECH PUBLIC(台舟)"))
      (libsource (lib "easyedapro") (part "BSS138_C18212695"))
    )
    (comp (ref "R19")
      (value "10kΩ")
      (footprint "easyedapro:R0603")
      (fields (field (name "Manufacturer Part") "RC0603FR-0710KL") (field (name "Manufacturer") "YAGEO(国巨)"))
      (libsource (lib "easyedapro") (part "RC0603FR-0710KL"))
    )
    (comp (ref "R20")
      (value "10kΩ")
      (footprint "easyedapro:R0603")
      (fields (field (name "Manufacturer Part") "RC0603FR-0710KL") (field (name "Manufacturer") "YAGEO(国巨)"))
      (libsource (lib "easyedapro") (part "RC0603FR-0710KL"))
    )
    (comp (ref "R21")
      (value "10kΩ")
      (footprint "easyedapro:R0603")
      (fields (field (name "Manufacturer Part") "RC0603FR-0710KL") (field (name "Manufacturer") "YAGEO(国巨)"))
      (libsource (lib "easyedapro") (part "RC0603FR-0710KL"))
    )
    (comp (ref "R22")
      (value "10kΩ")
      (footprint "easyedapro:R0603")
      (fields (field (name "Manufacturer Part") "RC0603FR-0710KL") (field (name "Manufacturer") "YAGEO(国巨)"))
      (libsource (lib "easyedapro") (part "RC0603FR-0710KL"))
    )
    (comp (ref "R23")
      (value "10kΩ")
      (footprint "easyedapro:R0603")
      (fields (field (name "Manufacturer Part") "RC0603FR-0710KL") (field (name "Manufacturer") "YAGEO(国巨)"))
      (libsource (lib "easyedapro") (part "RC0603FR-0710KL"))
    )
    (comp (ref "R24")
      (value "10kΩ")
      (footprint "easyedapro:R0603")
      (fields (field (name "Manufacturer Part") "RC0603FR-0710KL") (field (name "Manufacturer") "YAGEO(国巨)"))
      (libsource (lib "easyedapro") (part "RC0603FR-0710KL"))
    )
    (comp (ref "R25")
      (value "10kΩ")
      (footprint "easyedapro:R0603")
      (fields (field (name "Manufacturer Part") "RC0603FR-0710KL") (field (name "Manufacturer") "YAGEO(国巨)"))
      (libsource (lib "easyedapro") (part "RC0603FR-0710KL"))
    )
    (comp (ref "R26")
      (value "10kΩ")
      (footprint "easyedapro:R0603")
      (fields (field (name "Manufacturer Part") "RC0603FR-0710KL") (field (name "Manufacturer") "YAGEO(国巨)"))
      (libsource (lib "easyedapro") (part "RC0603FR-0710KL"))
    )
    (comp (ref "R27")
      (value "10kΩ")
      (footprint "easyedapro:R0603")
      (fields (field (name "Manufacturer Part") "RC0603FR-0710KL") (field (name "Manufacturer") "YAGEO(国巨)"))
      (libsource (lib "easyedapro") (part "RC0603FR-0710KL"))
    )
    (comp (ref "R28")
      (value "10kΩ")
      (footprint "easyedapro:R0603")
      (fields (field (name "Manufacturer Part") "RC0603FR-0710KL") (field (name "Manufacturer") "YAGEO(国巨)"))
      (libsource (lib "easyedapro") (part "RC0603FR-0710KL"))
    )
    (comp (ref "R29")
      (value "10kΩ")
      (footprint "easyedapro:R0603")
      (fields (field (name "Manufacturer Part") "RC0603FR-0710KL") (field (name "Manufacturer") "YAGEO(国巨)"))
      (libsource (lib "easyedapro") (part "RC0603FR-0710KL"))
    )
    (comp (ref "R30")
      (value "10kΩ")
      (footprint "easyedapro:R0603")
      (fields (field (name "Manufacturer Part") "RC0603FR-0710KL") (field (name "Manufacturer") "YAGEO(国巨)"))
      (libsource (lib "easyedapro") (part "RC0603FR-0710KL"))
    )
    (comp (ref "R31")
      (value "10kΩ")
      (footprint "easyedapro:R0603")
      (fields (field (name "Manufacturer Part") "RC0603FR-0710KL") (field (name "Manufacturer") "YAGEO(国巨)"))
      (libsource (lib "easyedapro") (part "RC0603FR-0710KL"))
    )
    (comp (ref "R32")
      (value "10kΩ")
      (footprint "easyedapro:R0603")
      (fields (field (name "Manufacturer Part") "RC0603FR-0710KL") (field (name "Manufacturer") "YAGEO(国巨)"))
      (libsource (lib "easyedapro") (part "RC0603FR-0710KL"))
    )
    (comp (ref "R33")
      (value "10kΩ")
      (footprint "easyedapro:R0603")
      (fields (field (name "Manufacturer Part") "RC0603FR-0710KL") (field (name "Manufacturer") "YAGEO(国巨)"))
      (libsource (lib "easyedapro") (part "RC0603FR-0710KL"))
    )
    (comp (ref "R34")
      (value "10kΩ")
      (footprint "easyedapro:R0603")
      (fields (field (name "Manufacturer Part") "RC0603FR-0710KL") (field (name "Manufacturer") "YAGEO(国巨)"))
      (libsource (lib "easyedapro") (part "RC0603FR-0710KL"))
    )
    (comp (ref "SONAR0")
      (value "ZX-XH2.54-4PZZ")
      (footprint "easyedapro:CONN-TH_4P-P2.50_4PIN")
      (fields (field (name "Manufacturer") "Megastar(兆星)"))
      (libsource (lib "easyedapro") (part "ZX-XH2.54-4PZZ"))
    )
    (comp (ref "SONAR1")
      (value "ZX-XH2.54-4PZZ")
      (footprint "easyedapro:CONN-TH_4P-P2.50_4PIN")
      (fields (field (name "Manufacturer") "Megastar(兆星)"))
      (libsource (lib "easyedapro") (part "ZX-XH2.54-4PZZ"))
    )
    (comp (ref "SONAR2")
      (value "ZX-XH2.54-4PZZ")
      (footprint "easyedapro:CONN-TH_4P-P2.50_4PIN")
      (fields (field (name "Manufacturer") "Megastar(兆星)"))
      (libsource (lib "easyedapro") (part "ZX-XH2.54-4PZZ"))
    )
    (comp (ref "SONAR3")
      (value "ZX-XH2.54-4PZZ")
      (footprint "easyedapro:CONN-TH_4P-P2.50_4PIN")
      (fields (field (name "Manufacturer") "Megastar(兆星)"))
      (libsource (lib "easyedapro") (part "ZX-XH2.54-4PZZ"))
    )
    (comp (ref "CN1")
      (value "ZX-XH2.54-3PZZ")
      (footprint "easyedapro:CONN-TH_3P-P2.54_2501S-3P")
      (fields (field (name "Manufacturer") "Megastar(兆星)"))
      (libsource (lib "easyedapro") (part "ZX-XH2.54-3PZZ"))
    )
    (comp (ref "CN2")
      (value "ZX-XH2.54-3PZZ")
      (footprint "easyedapro:CONN-TH_3P-P2.54_2501S-3P")
      (fields (field (name "Manufacturer") "Megastar(兆星)"))
      (libsource (lib "easyedapro") (part "ZX-XH2.54-3PZZ"))
    )
    (comp (ref "CN3")
      (value "ZX-XH2.54-3PZZ")
      (footprint "easyedapro:CONN-TH_3P-P2.54_2501S-3P")
      (fields (field (name "Manufacturer") "Megastar(兆星)"))
      (libsource (lib "easyedapro") (part "ZX-XH2.54-3PZZ"))
    )
    (comp (ref "CN50")
      (value "ZX-XH2.54-3PZZ")
      (footprint "easyedapro:CONN-TH_3P-P2.54_2501S-3P")
      (fields (field (name "Manufacturer") "Megastar(兆星)"))
      (libsource (lib "easyedapro") (part "ZX-XH2.54-3PZZ"))
    )
    (comp (ref "CN51")
      (value "ZX-XH2.54-3PZZ")
      (footprint "easyedapro:CONN-TH_3P-P2.54_2501S-3P")
      (fields (field (name "Manufacturer") "Megastar(兆星)"))
      (libsource (lib "easyedapro") (part "ZX-XH2.54-3PZZ"))
    )
    (comp (ref "CN52")
      (value "ZX-XH2.54-3PZZ")
      (footprint "easyedapro:CONN-TH_3P-P2.54_2501S-3P")
      (fields (field (name "Manufacturer") "Megastar(兆星)"))
      (libsource (lib "easyedapro") (part "ZX-XH2.54-3PZZ"))
    )
    (comp (ref "CN53")
      (value "ZX-XH2.54-3PZZ")
      (footprint "easyedapro:CONN-TH_3P-P2.54_2501S-3P")
      (fields (field (name "Manufacturer") "Megastar(兆星)"))
      (libsource (lib "easyedapro") (part "ZX-XH2.54-3PZZ"))
    )
    (comp (ref "CN54")
      (value "ZX-XH2.54-3PZZ")
      (footprint "easyedapro:CONN-TH_3P-P2.54_2501S-3P")
      (fields (field (name "Manufacturer") "Megastar(兆星)"))
      (libsource (lib "easyedapro") (part "ZX-XH2.54-3PZZ"))
    )
    (comp (ref "H1")
      (value "PZ254V-11-03P")
      (footprint "easyedapro:HDR-TH_3P-P2.54-V-M")
      (fields (field (name "Manufacturer") "XFCN(兴飞)"))
      (libsource (lib "easyedapro") (part "PZ254V-11-03P_C2937625"))
    )
    (comp (ref "P2")
      (value "WJ127-5.0-2P")
      (footprint "easyedapro:CONN-TH_2P-P5.00_CPC3703CTR")
      (fields (field (name "Manufacturer") "KANGNEX(康奈克斯电气)"))
      (libsource (lib "easyedapro") (part "WJ127-5.0-2P"))
    )
    (comp (ref "Q16")
      (value "BSS138")
      (footprint "easyedapro:SOT-23-3_L2.9-W1.6-P1.90-LS2.8-BR")
      (fields (field (name "Manufacturer") "TECH PUBLIC(台舟)"))
      (libsource (lib "easyedapro") (part "BSS138_C18212695"))
    )
    (comp (ref "Q19")
      (value "BSS138")
      (footprint "easyedapro:SOT-23-3_L2.9-W1.6-P1.90-LS2.8-BR")
      (fields (field (name "Manufacturer") "TECH PUBLIC(台舟)"))
      (libsource (lib "easyedapro") (part "BSS138_C18212695"))
    )
    (comp (ref "Q20")
      (value "BSS138")
      (footprint "easyedapro:SOT-23-3_L2.9-W1.6-P1.90-LS2.8-BR")
      (fields (field (name "Manufacturer") "TECH PUBLIC(台舟)"))
      (libsource (lib "easyedapro") (part "BSS138_C18212695"))
    )
    (comp (ref "Q21")
      (value "BSS138")
      (footprint "easyedapro:SOT-23-3_L2.9-W1.6-P1.90-LS2.8-BR")
      (fields (field (name "Manufacturer") "TECH PUBLIC(台舟)"))
      (libsource (lib "easyedapro") (part "BSS138_C18212695"))
    )
    (comp (ref "R39")
      (value "10kΩ")
      (footprint "easyedapro:R0603")
      (fields (field (name "Manufacturer Part") "RC0603FR-0710KL") (field (name "Manufacturer") "YAGEO(国巨)"))
      (libsource (lib "easyedapro") (part "RC0603FR-0710KL"))
    )
    (comp (ref "R40")
      (value "10kΩ")
      (footprint "easyedapro:R0603")
      (fields (field (name "Manufacturer Part") "RC0603FR-0710KL") (field (name "Manufacturer") "YAGEO(国巨)"))
      (libsource (lib "easyedapro") (part "RC0603FR-0710KL"))
    )
    (comp (ref "R41")
      (value "10kΩ")
      (footprint "easyedapro:R0603")
      (fields (field (name "Manufacturer Part") "RC0603FR-0710KL") (field (name "Manufacturer") "YAGEO(国巨)"))
      (libsource (lib "easyedapro") (part "RC0603FR-0710KL"))
    )
    (comp (ref "R42")
      (value "10kΩ")
      (footprint "easyedapro:R0603")
      (fields (field (name "Manufacturer Part") "RC0603FR-0710KL") (field (name "Manufacturer") "YAGEO(国巨)"))
      (libsource (lib "easyedapro") (part "RC0603FR-0710KL"))
    )
    (comp (ref "R43")
      (value "10kΩ")
      (footprint "easyedapro:R0603")
      (fields (field (name "Manufacturer Part") "RC0603FR-0710KL") (field (name "Manufacturer") "YAGEO(国巨)"))
      (libsource (lib "easyedapro") (part "RC0603FR-0710KL"))
    )
    (comp (ref "R44")
      (value "10kΩ")
      (footprint "easyedapro:R0603")
      (fields (field (name "Manufacturer Part") "RC0603FR-0710KL") (field (name "Manufacturer") "YAGEO(国巨)"))
      (libsource (lib "easyedapro") (part "RC0603FR-0710KL"))
    )
    (comp (ref "R45")
      (value "10kΩ")
      (footprint "easyedapro:R0603")
      (fields (field (name "Manufacturer Part") "RC0603FR-0710KL") (field (name "Manufacturer") "YAGEO(国巨)"))
      (libsource (lib "easyedapro") (part "RC0603FR-0710KL"))
    )
    (comp (ref "R46")
      (value "10kΩ")
      (footprint "easyedapro:R0603")
      (fields (field (name "Manufacturer Part") "RC0603FR-0710KL") (field (name "Manufacturer") "YAGEO(国巨)"))
      (libsource (lib "easyedapro") (part "RC0603FR-0710KL"))
    )
    (comp (ref "U19")
      (value "BX-PZ2.54-2-3PZZ")
      (footprint "easyedapro:HDR-TH_6P-P2.54-V-M-R2-C3-S2.54")
      (fields (field (name "Manufacturer") "Bossie(博锡)"))
      (libsource (lib "easyedapro") (part "BX-PZ2.54-2-3PZZ"))
    )
  )
  (nets
    (net (code "1") (name "3.3V") (class "Default")
      (node (ref "CN10") (pin "1") (pinfunction "1_1") (pintype "unspecified"))
      (node (ref "CN11") (pin "1") (pinfunction "1_1") (pintype "unspecified"))
      (node (ref "CN12") (pin "1") (pinfunction "1_1") (pintype "unspecified"))
      (node (ref "CN13") (pin "1") (pinfunction "1_1") (pintype "unspecified"))
      (node (ref "CN14") (pin "1") (pinfunction "1_1") (pintype "unspecified"))
      (node (ref "CN15") (pin "1") (pinfunction "1_1") (pintype "unspecified"))
      (node (ref "CN16") (pin "1") (pinfunction "1_1") (pintype "unspecified"))
      (node (ref "CN17") (pin "1") (pinfunction "1_1") (pintype "unspecified"))
      (node (ref "CN18") (pin "1") (pinfunction "1_1") (pintype "unspecified"))
      (node (ref "CN19") (pin "1") (pinfunction "1_1") (pintype "unspecified"))
      (node (ref "CN20") (pin "1") (pinfunction "1_1") (pintype "unspecified"))
      (node (ref "CN21") (pin "1") (pinfunction "1_1") (pintype "unspecified"))
      (node (ref "CN56") (pin "1") (pinfunction "1_1") (pintype "unspecified"))
      (node (ref "CN57") (pin "1") (pinfunction "1_1") (pintype "unspecified"))
      (node (ref "CN58") (pin "1") (pinfunction "1_1") (pintype "unspecified"))
      (node (ref "CN59") (pin "1") (pinfunction "1_1") (pintype "unspecified"))
      (node (ref "CN60") (pin "1") (pinfunction "1_1") (pintype "unspecified"))
      (node (ref "CN61") (pin "1") (pinfunction "1_1") (pintype "unspecified"))
      (node (ref "CN62") (pin "1") (pinfunction "1_1") (pintype "unspecified"))
      (node (ref "CN63") (pin "1") (pinfunction "1_1") (pintype "unspecified"))
      (node (ref "Q1") (pin "1") (pinfunction "G_1") (pintype "unspecified"))
      (node (ref "Q16") (pin "1") (pinfunction "G_1") (pintype "unspecified"))
      (node (ref "Q19") (pin "1") (pinfunction "G_1") (pintype "unspecified"))
      (node (ref "Q2") (pin "1") (pinfunction "G_1") (pintype "unspecified"))
      (node (ref "Q20") (pin "1") (pinfunction "G_1") (pintype "unspecified"))
      (node (ref "Q21") (pin "1") (pinfunction "G_1") (pintype "unspecified"))
      (node (ref "Q3") (pin "1") (pinfunction "G_1") (pintype "unspecified"))
      (node (ref "Q4") (pin "1") (pinfunction "G_1") (pintype "unspecified"))
      (node (ref "Q5") (pin "1") (pinfunction "G_1") (pintype "unspecified"))
      (node (ref "Q6") (pin "1") (pinfunction "G_1") (pintype "unspecified"))
      (node (ref "Q7") (pin "1") (pinfunction "G_1") (pintype "unspecified"))
      (node (ref "Q8") (pin "1") (pinfunction "G_1") (pintype "unspecified"))
      (node (ref "R1") (pin "1") (pinfunction "1_1") (pintype "input"))
      (node (ref "R10") (pin "2") (pinfunction "2_2") (pintype "input"))
      (node (ref "R11") (pin "2") (pinfunction "2_2") (pintype "input"))
      (node (ref "R12") (pin "2") (pinfunction "2_2") (pintype "input"))
      (node (ref "R13") (pin "2") (pinfunction "2_2") (pintype "input"))
      (node (ref "R14") (pin "2") (pinfunction "2_2") (pintype "input"))
      (node (ref "R15") (pin "2") (pinfunction "2_2") (pintype "input"))
      (node (ref "R16") (pin "2") (pinfunction "2_2") (pintype "input"))
      (node (ref "R17") (pin "2") (pinfunction "2_2") (pintype "input"))
      (node (ref "R18") (pin "2") (pinfunction "2_2") (pintype "input"))
      (node (ref "R2") (pin "1") (pinfunction "1_1") (pintype "input"))
      (node (ref "R20") (pin "1") (pinfunction "1_1") (pintype "input"))
      (node (ref "R22") (pin "2") (pinfunction "2_2") (pintype "input"))
      (node (ref "R24") (pin "1") (pinfunction "1_1") (pintype "input"))
      (node (ref "R26") (pin "2") (pinfunction "2_2") (pintype "input"))
      (node (ref "R28") (pin "1") (pinfunction "1_1") (pintype "input"))
      (node (ref "R3") (pin "1") (pinfunction "1_1") (pintype "input"))
      (node (ref "R30") (pin "2") (pinfunction "2_2") (pintype "input"))
      (node (ref "R32") (pin "1") (pinfunction "1_1") (pintype "input"))
      (node (ref "R34") (pin "2") (pinfunction "2_2") (pintype "input"))
      (node (ref "R39") (pin "2") (pinfunction "2_2") (pintype "input"))
      (node (ref "R4") (pin "1") (pinfunction "1_1") (pintype "input"))
      (node (ref "R41") (pin "2") (pinfunction "2_2") (pintype "input"))
      (node (ref "R43") (pin "2") (pinfunction "2_2") (pintype "input"))
      (node (ref "R45") (pin "2") (pinfunction "2_2") (pintype "input"))
      (node (ref "R5") (pin "1") (pinfunction "1_1") (pintype "input"))
      (node (ref "R6") (pin "1") (pinfunction "1_1") (pintype "input"))
      (node (ref "R7") (pin "1") (pinfunction "1_1") (pintype "input"))
      (node (ref "R8") (pin "1") (pinfunction "1_1") (pintype "input"))
      (node (ref "R9") (pin "2") (pinfunction "2_2") (pintype "input"))
      (node (ref "U1") (pin "15") (pinfunction "3.3V_15") (pintype "unspecified"))
      (node (ref "U1") (pin "46") (pinfunction "3.3V_46") (pintype "unspecified"))
      (node (ref "U19") (pin "1") (pinfunction "1_1") (pintype "unspecified"))
      (node (ref "U2") (pin "24") (pinfunction "VCC_24") (pintype "unspecified"))
      (node (ref "U43") (pin "3") (pinfunction "3_3") (pintype "unspecified"))
      (node (ref "U44") (pin "15") (pinfunction "15_15") (pintype "unspecified"))
      (node (ref "U5") (pin "1") (pinfunction "1_1") (pintype "unspecified"))
      (node (ref "U6") (pin "1") (pinfunction "1_1") (pintype "unspecified"))
    )
    (net (code "2") (name "5V") (class "Default")
      (node (ref "H1") (pin "1") (pinfunction "1_1") (pintype "unspecified"))
      (node (ref "P1") (pin "2") (pinfunction "2_2") (pintype "input"))
      (node (ref "R19") (pin "1") (pinfunction "1_1") (pintype "input"))
      (node (ref "R21") (pin "2") (pinfunction "2_2") (pintype "input"))
      (node (ref "R23") (pin "1") (pinfunction "1_1") (pintype "input"))
      (node (ref "R25") (pin "2") (pinfunction "2_2") (pintype "input"))
      (node (ref "R27") (pin "1") (pinfunction "1_1") (pintype "input"))
      (node (ref "R29") (pin "2") (pinfunction "2_2") (pintype "input"))
      (node (ref "R31") (pin "1") (pinfunction "1_1") (pintype "input"))
      (node (ref "R33") (pin "2") (pinfunction "2_2") (pintype "input"))
      (node (ref "SONAR0") (pin "1") (pinfunction "1_1") (pintype "unspecified"))
      (node (ref "SONAR1") (pin "1") (pinfunction "1_1") (pintype "unspecified"))
      (node (ref "SONAR2") (pin "1") (pinfunction "1_1") (pintype "unspecified"))
      (node (ref "SONAR3") (pin "1") (pinfunction "1_1") (pintype "unspecified"))
      (node (ref "U1") (pin "48") (pinfunction "VIN_48") (pintype "unspecified"))
      (node (ref "U19") (pin "3") (pinfunction "3_3") (pintype "unspecified"))
      (node (ref "U4") (pin "1") (pinfunction "1_1") (pintype "unspecified"))
      (node (ref "U43") (pin "1") (pinfunction "1_1") (pintype "unspecified"))
      (node (ref "U8") (pin "1") (pinfunction "1_1") (pintype "unspecified"))
    )
    (net (code "3") (name "A10") (class "Default")
      (node (ref "CN63") (pin "3") (pinfunction "3_3") (pintype "unspecified"))
      (node (ref "U1") (pin "16") (pinfunction "SCL2/TX6/A10_16") (pintype "unspecified"))
      (node (ref "U44") (pin "16") (pinfunction "16_16") (pintype "unspecified"))
    )
    (net (code "4") (name "A11") (class "Default")
      (node (ref "CN62") (pin "3") (pinfunction "3_3") (pintype "unspecified"))
      (node (ref "U1") (pin "17") (pinfunction "SDA2/RX6/A11_17") (pintype "unspecified"))
      (node (ref "U44") (pin "17") (pinfunction "17_17") (pintype "unspecified"))
    )
    (net (code "5") (name "A12") (class "Default")
      (node (ref "CN61") (pin "3") (pinfunction "3_3") (pintype "unspecified"))
      (node (ref "U1") (pin "18") (pinfunction "MOSI1/A12_18") (pintype "unspecified"))
      (node (ref "U44") (pin "18") (pinfunction "18_18") (pintype "unspecified"))
    )
    (net (code "6") (name "A13") (class "Default")
      (node (ref "CN60") (pin "3") (pinfunction "3_3") (pintype "unspecified"))
      (node (ref "U1") (pin "19") (pinfunction "SCK1/A13_19") (pintype "unspecified"))
      (node (ref "U44") (pin "19") (pinfunction "19_19") (pintype "unspecified"))
    )
    (net (code "7") (name "A14") (class "Default")
      (node (ref "CN59") (pin "3") (pinfunction "3_3") (pintype "unspecified"))
      (node (ref "U1") (pin "30") (pinfunction "INN/CS1/A14_30") (pintype "unspecified"))
      (node (ref "U43") (pin "19") (pinfunction "19_19") (pintype "unspecified"))
    )
    (net (code "8") (name "A15") (class "Default")
      (node (ref "CN58") (pin "3") (pinfunction "3_3") (pintype "unspecified"))
      (node (ref "U1") (pin "31") (pinfunction "OUT1A/MISO1/A15_31") (pintype "unspecified"))
      (node (ref "U43") (pin "18") (pinfunction "18_18") (pintype "unspecified"))
    )
    (net (code "9") (name "A16") (class "Default")
      (node (ref "CN57") (pin "3") (pinfunction "3_3") (pintype "unspecified"))
      (node (ref "U1") (pin "32") (pinfunction "A16_32") (pintype "unspecified"))
      (node (ref "U43") (pin "17") (pinfunction "17_17") (pintype "unspecified"))
    )
    (net (code "10") (name "A17") (class "Default")
      (node (ref "CN56") (pin "3") (pinfunction "3_3") (pintype "unspecified"))
      (node (ref "U1") (pin "33") (pinfunction "A17_33") (pintype "unspecified"))
      (node (ref "U43") (pin "16") (pinfunction "16_16") (pintype "unspecified"))
    )
    (net (code "11") (name "BCLK2") (class "Default")
      (node (ref "CN50") (pin "3") (pinfunction "3_3") (pintype "unspecified"))
      (node (ref "U1") (pin "6") (pinfunction "BCLK2_6") (pintype "unspecified"))
      (node (ref "U44") (pin "6") (pinfunction "6_6") (pintype "unspecified"))
    )
    (net (code "12") (name "CRX1") (class "Default")
      (node (ref "CN10") (pin "3") (pinfunction "3_3") (pintype "unspecified"))
      (node (ref "U1") (pin "45") (pinfunction "CRX1/A9_45") (pintype "unspecified"))
      (node (ref "U43") (pin "4") (pinfunction "4_4") (pintype "unspecified"))
    )
    (net (code "13") (name "CRX3") (class "Default")
      (node (ref "U1") (pin "22") (pinfunction "CRX3_22") (pintype "unspecified"))
      (node (ref "U44") (pin "22") (pinfunction "22_22") (pintype "unspecified"))
      (node (ref "U5") (pin "5") (pinfunction "5_5") (pintype "unspecified"))
    )
    (net (code "14") (name "CS") (class "Default")
      (node (ref "U1") (pin "12") (pinfunction "MQSR/CS_12") (pintype "unspecified"))
      (node (ref "U4") (pin "6") (pinfunction "6_6") (pintype "unspecified"))
      (node (ref "U44") (pin "12") (pinfunction "12_12") (pintype "unspecified"))
    )
    (net (code "15") (name "CTX1") (class "Default")
      (node (ref "CN10") (pin "4") (pinfunction "4_4") (pintype "unspecified"))
      (node (ref "U1") (pin "44") (pinfunction "CTX1/A8_44") (pintype "unspecified"))
      (node (ref "U43") (pin "5") (pinfunction "5_5") (pintype "unspecified"))
    )
    (net (code "16") (name "CTX3") (class "Default")
      (node (ref "U1") (pin "23") (pinfunction "CTX3_23") (pintype "unspecified"))
      (node (ref "U44") (pin "23") (pinfunction "23_23") (pintype "unspecified"))
      (node (ref "U6") (pin "5") (pinfunction "5_5") (pintype "unspecified"))
    )
    (net (code "17") (name "ECHO0") (class "Default")
      (node (ref "Q2") (pin "3") (pinfunction "D_3") (pintype "unspecified"))
      (node (ref "R22") (pin "1") (pinfunction "1_1") (pintype "input"))
      (node (ref "U1") (pin "25") (pinfunction "MCLK2_25") (pintype "unspecified"))
      (node (ref "U43") (pin "24") (pinfunction "24_24") (pintype "unspecified"))
    )
    (net (code "18") (name "ECHO1") (class "Default")
      (node (ref "Q4") (pin "3") (pinfunction "D_3") (pintype "unspecified"))
      (node (ref "R26") (pin "1") (pinfunction "1_1") (pintype "input"))
      (node (ref "U1") (pin "27") (pinfunction "TX8_27") (pintype "unspecified"))
      (node (ref "U43") (pin "22") (pinfunction "22_22") (pintype "unspecified"))
    )
    (net (code "19") (name "ECHO2") (class "Default")
      (node (ref "Q6") (pin "3") (pinfunction "D_3") (pintype "unspecified"))
      (node (ref "R30") (pin "1") (pinfunction "1_1") (pintype "input"))
      (node (ref "U1") (pin "29") (pinfunction "CS_29") (pintype "unspecified"))
      (node (ref "U43") (pin "20") (pinfunction "20_20") (pintype "unspecified"))
    )
    (net (code "20") (name "ECHO3") (class "Default")
      (node (ref "Q8") (pin "3") (pinfunction "D_3") (pintype "unspecified"))
      (node (ref "R34") (pin "1") (pinfunction "1_1") (pintype "input"))
      (node (ref "U1") (pin "37") (pinfunction "RX3/A1_37") (pintype "unspecified"))
      (node (ref "U43") (pin "12") (pinfunction "12_12") (pintype "unspecified"))
    )
    (net (code "21") (name "GND") (class "Default")
      (node (ref "CN1") (pin "2") (pinfunction "2_2") (pintype "unspecified"))
      (node (ref "CN10") (pin "2") (pinfunction "2_2") (pintype "unspecified"))
      (node (ref "CN11") (pin "2") (pinfunction "2_2") (pintype "unspecified"))
      (node (ref "CN12") (pin "2") (pinfunction "2_2") (pintype "unspecified"))
      (node (ref "CN13") (pin "2") (pinfunction "2_2") (pintype "unspecified"))
      (node (ref "CN14") (pin "2") (pinfunction "2_2") (pintype "unspecified"))
      (node (ref "CN15") (pin "2") (pinfunction "2_2") (pintype "unspecified"))
      (node (ref "CN16") (pin "2") (pinfunction "2_2") (pintype "unspecified"))
      (node (ref "CN17") (pin "2") (pinfunction "2_2") (pintype "unspecified"))
      (node (ref "CN18") (pin "2") (pinfunction "2_2") (pintype "unspecified"))
      (node (ref "CN19") (pin "2") (pinfunction "2_2") (pintype "unspecified"))
      (node (ref "CN2") (pin "2") (pinfunction "2_2") (pintype "unspecified"))
      (node (ref "CN20") (pin "2") (pinfunction "2_2") (pintype "unspecified"))
      (node (ref "CN21") (pin "2") (pinfunction "2_2") (pintype "unspecified"))
      (node (ref "CN3") (pin "2") (pinfunction "2_2") (pintype "unspecified"))
      (node (ref "CN50") (pin "2") (pinfunction "2_2") (pintype "unspecified"))
      (node (ref "CN51") (pin "2") (pinfunction "2_2") (pintype "unspecified"))
      (node (ref "CN52") (pin "2") (pinfunction "2_2") (pintype "unspecified"))
      (node (ref "CN53") (pin "2") (pinfunction "2_2") (pintype "unspecified"))
      (node (ref "CN54") (pin "2") (pinfunction "2_2") (pintype "unspecified"))
      (node (ref "CN56") (pin "2") (pinfunction "2_2") (pintype "unspecified"))
      (node (ref "CN57") (pin "2") (pinfunction "2_2") (pintype "unspecified"))
      (node (ref "CN58") (pin "2") (pinfunction "2_2") (pintype "unspecified"))
      (node (ref "CN59") (pin "2") (pinfunction "2_2") (pintype "unspecified"))
      (node (ref "CN60") (pin "2") (pinfunction "2_2") (pintype "unspecified"))
      (node (ref "CN61") (pin "2") (pinfunction "2_2") (pintype "unspecified"))
      (node (ref "CN62") (pin "2") (pinfunction "2_2") (pintype "unspecified"))
      (node (ref "CN63") (pin "2") (pinfunction "2_2") (pintype "unspecified"))
      (node (ref "H18") (pin "1") (pinfunction "1_1") (pintype "unspecified"))
      (node (ref "H18") (pin "3") (pinfunction "3_3") (pintype "unspecified"))
      (node (ref "P1") (pin "1") (pinfunction "1_1") (pintype "input"))
      (node (ref "P2") (pin "1") (pinfunction "1_1") (pintype "input"))
      (node (ref "SONAR0") (pin "2") (pinfunction "2_2") (pintype "unspecified"))
      (node (ref "SONAR1") (pin "2") (pinfunction "2_2") (pintype "unspecified"))
      (node (ref "SONAR2") (pin "2") (pinfunction "2_2") (pintype "unspecified"))
      (node (ref "SONAR3") (pin "2") (pinfunction "2_2") (pintype "unspecified"))
      (node (ref "U1") (pin "1") (pinfunction "GND_1") (pintype "unspecified"))
      (node (ref "U1") (pin "34") (pinfunction "GND_34") (pintype "unspecified"))
      (node (ref "U1") (pin "47") (pinfunction "GND_47") (pintype "unspecified"))
      (node (ref "U2") (pin "1") (pinfunction "A0_1") (pintype "unspecified"))
      (node (ref "U2") (pin "12") (pinfunction "GND_12") (pintype "unspecified"))
      (node (ref "U2") (pin "2") (pinfunction "A1_2") (pintype "unspecified"))
      (node (ref "U2") (pin "21") (pinfunction "A2_21") (pintype "unspecified"))
      (node (ref "U4") (pin "2") (pinfunction "2_2") (pintype "unspecified"))
      (node (ref "U43") (pin "15") (pinfunction "15_15") (pintype "unspecified"))
      (node (ref "U43") (pin "2") (pinfunction "2_2") (pintype "unspecified"))
      (node (ref "U44") (pin "1") (pinfunction "1_1") (pintype "unspecified"))
      (node (ref "U48") (pin "3") (pinfunction "3_3") (pintype "input"))
      (node (ref "U5") (pin "2") (pinfunction "2_2") (pintype "unspecified"))
      (node (ref "U6") (pin "2") (pinfunction "2_2") (pintype "unspecified"))
      (node (ref "U8") (pin "2") (pinfunction "2_2") (pintype "unspecified"))
    )
    (net (code "22") (name "I2CRESET") (class "Default")
      (node (ref "U1") (pin "10") (pinfunction "IN1/TX2_10") (pintype "unspecified"))
      (node (ref "U2") (pin "3") (pinfunction "RESET#_3") (pintype "unspecified"))
      (node (ref "U44") (pin "10") (pinfunction "10_10") (pintype "unspecified"))
    )
    (net (code "23") (name "IN2") (class "Default")
      (node (ref "CN51") (pin "3") (pinfunction "3_3") (pintype "unspecified"))
      (node (ref "U1") (pin "7") (pinfunction "IN2_7") (pintype "unspecified"))
      (node (ref "U44") (pin "7") (pinfunction "7_7") (pintype "unspecified"))
    )
    (net (code "24") (name "LRCLK2") (class "Default")
      (node (ref "Q16") (pin "2") (pinfunction "S_2") (pintype "unspecified"))
      (node (ref "R39") (pin "1") (pinfunction "1_1") (pintype "input"))
      (node (ref "U1") (pin "5") (pinfunction "LRCLK2_5") (pintype "unspecified"))
      (node (ref "U44") (pin "5") (pinfunction "5_5") (pintype "unspecified"))
    )
    (net (code "25") (name "MISO") (class "Default")
      (node (ref "U1") (pin "14") (pinfunction "MQSL/MISO_14") (pintype "unspecified"))
      (node (ref "U4") (pin "4") (pinfunction "4_4") (pintype "unspecified"))
      (node (ref "U44") (pin "14") (pinfunction "14_14") (pintype "unspecified"))
      (node (ref "U8") (pin "4") (pinfunction "4_4") (pintype "unspecified"))
    )
    (net (code "26") (name "MOSI") (class "Default")
      (node (ref "U1") (pin "13") (pinfunction "CTX1/MOSI_13") (pintype "unspecified"))
      (node (ref "U4") (pin "3") (pinfunction "3_3") (pintype "unspecified"))
      (node (ref "U44") (pin "13") (pinfunction "13_13") (pintype "unspecified"))
      (node (ref "U8") (pin "3") (pinfunction "3_3") (pintype "unspecified"))
    )
    (net (code "27") (name "Net-(CN1-Pad1)") (class "Default")
      (node (ref "CN1") (pin "1") (pinfunction "1_1") (pintype "unspecified"))
      (node (ref "CN2") (pin "1") (pinfunction "1_1") (pintype "unspecified"))
      (node (ref "CN3") (pin "1") (pinfunction "1_1") (pintype "unspecified"))
      (node (ref "CN54") (pin "1") (pinfunction "1_1") (pintype "unspecified"))
      (node (ref "R40") (pin "2") (pinfunction "2_2") (pintype "input"))
      (node (ref "R42") (pin "2") (pinfunction "2_2") (pintype "input"))
      (node (ref "R44") (pin "2") (pinfunction "2_2") (pintype "input"))
      (node (ref "R46") (pin "2") (pinfunction "2_2") (pintype "input"))
      (node (ref "U19") (pin "2") (pinfunction "2_2") (pintype "unspecified"))
      (node (ref "U19") (pin "4") (pinfunction "4_4") (pintype "unspecified"))
      (node (ref "U19") (pin "6") (pinfunction "6_6") (pintype "unspecified"))
    )
    (net (code "28") (name "Net-(CN50-Pad1)") (class "Default")
      (node (ref "CN50") (pin "1") (pinfunction "1_1") (pintype "unspecified"))
      (node (ref "CN51") (pin "1") (pinfunction "1_1") (pintype "unspecified"))
      (node (ref "CN52") (pin "1") (pinfunction "1_1") (pintype "unspecified"))
      (node (ref "CN53") (pin "1") (pinfunction "1_1") (pintype "unspecified"))
      (node (ref "H1") (pin "2") (pinfunction "2_2") (pintype "unspecified"))
    )
    (net (code "29") (name "Net-(H1-Pad3)") (class "Default")
      (node (ref "H1") (pin "3") (pinfunction "3_3") (pintype "unspecified"))
      (node (ref "P2") (pin "2") (pinfunction "2_2") (pintype "input"))
      (node (ref "U19") (pin "5") (pinfunction "5_5") (pintype "unspecified"))
    )
    (net (code "30") (name "Net-(Q1-D)") (class "Default")
      (node (ref "Q1") (pin "3") (pinfunction "D_3") (pintype "unspecified"))
      (node (ref "R19") (pin "2") (pinfunction "2_2") (pintype "input"))
      (node (ref "SONAR0") (pin "3") (pinfunction "3_3") (pintype "unspecified"))
    )
    (net (code "31") (name "Net-(Q2-S)") (class "Default")
      (node (ref "Q2") (pin "2") (pinfunction "S_2") (pintype "unspecified"))
      (node (ref "R21") (pin "1") (pinfunction "1_1") (pintype "input"))
      (node (ref "SONAR0") (pin "4") (pinfunction "4_4") (pintype "unspecified"))
    )
    (net (code "32") (name "Net-(Q3-D)") (class "Default")
      (node (ref "Q3") (pin "3") (pinfunction "D_3") (pintype "unspecified"))
      (node (ref "R23") (pin "2") (pinfunction "2_2") (pintype "input"))
      (node (ref "SONAR1") (pin "3") (pinfunction "3_3") (pintype "unspecified"))
    )
    (net (code "33") (name "Net-(Q4-S)") (class "Default")
      (node (ref "Q4") (pin "2") (pinfunction "S_2") (pintype "unspecified"))
      (node (ref "R25") (pin "1") (pinfunction "1_1") (pintype "input"))
      (node (ref "SONAR1") (pin "4") (pinfunction "4_4") (pintype "unspecified"))
    )
    (net (code "34") (name "Net-(Q5-D)") (class "Default")
      (node (ref "Q5") (pin "3") (pinfunction "D_3") (pintype "unspecified"))
      (node (ref "R27") (pin "2") (pinfunction "2_2") (pintype "input"))
      (node (ref "SONAR2") (pin "3") (pinfunction "3_3") (pintype "unspecified"))
    )
    (net (code "35") (name "Net-(Q6-S)") (class "Default")
      (node (ref "Q6") (pin "2") (pinfunction "S_2") (pintype "unspecified"))
      (node (ref "R29") (pin "1") (pinfunction "1_1") (pintype "input"))
      (node (ref "SONAR2") (pin "4") (pinfunction "4_4") (pintype "unspecified"))
    )
    (net (code "36") (name "Net-(Q7-D)") (class "Default")
      (node (ref "Q7") (pin "3") (pinfunction "D_3") (pintype "unspecified"))
      (node (ref "R31") (pin "2") (pinfunction "2_2") (pintype "input"))
      (node (ref "SONAR3") (pin "3") (pinfunction "3_3") (pintype "unspecified"))
    )
    (net (code "37") (name "Net-(Q8-S)") (class "Default")
      (node (ref "Q8") (pin "2") (pinfunction "S_2") (pintype "unspecified"))
      (node (ref "R33") (pin "1") (pinfunction "1_1") (pintype "input"))
      (node (ref "SONAR3") (pin "4") (pinfunction "4_4") (pintype "unspecified"))
    )
    (net (code "38") (name "Net-(Q16-D)") (class "Default")
      (node (ref "CN1") (pin "3") (pinfunction "3_3") (pintype "unspecified"))
      (node (ref "Q16") (pin "3") (pinfunction "D_3") (pintype "unspecified"))
      (node (ref "R40") (pin "1") (pinfunction "1_1") (pintype "input"))
    )
    (net (code "39") (name "Net-(Q19-D)") (class "Default")
      (node (ref "CN2") (pin "3") (pinfunction "3_3") (pintype "unspecified"))
      (node (ref "Q19") (pin "3") (pinfunction "D_3") (pintype "unspecified"))
      (node (ref "R42") (pin "1") (pinfunction "1_1") (pintype "input"))
    )
    (net (code "40") (name "Net-(Q20-D)") (class "Default")
      (node (ref "CN54") (pin "3") (pinfunction "3_3") (pintype "unspecified"))
      (node (ref "Q20") (pin "3") (pinfunction "D_3") (pintype "unspecified"))
      (node (ref "R44") (pin "1") (pinfunction "1_1") (pintype "input"))
    )
    (net (code "41") (name "Net-(Q21-D)") (class "Default")
      (node (ref "CN3") (pin "3") (pinfunction "3_3") (pintype "unspecified"))
      (node (ref "Q21") (pin "3") (pinfunction "D_3") (pintype "unspecified"))
      (node (ref "R46") (pin "1") (pinfunction "1_1") (pintype "input"))
    )
    (net (code "42") (name "Net-(U2-SC0)") (class "Default")
      (node (ref "CN14") (pin "3") (pinfunction "3_3") (pintype "unspecified"))
      (node (ref "R2") (pin "2") (pinfunction "2_2") (pintype "input"))
      (node (ref "U2") (pin "5") (pinfunction "SC0_5") (pintype "unspecified"))
    )
    (net (code "43") (name "Net-(U2-SC1)") (class "Default")
      (node (ref "CN15") (pin "3") (pinfunction "3_3") (pintype "unspecified"))
      (node (ref "R4") (pin "2") (pinfunction "2_2") (pintype "input"))
      (node (ref "U2") (pin "7") (pinfunction "SC1_7") (pintype "unspecified"))
    )
    (net (code "44") (name "Net-(U2-SC2)") (class "Default")
      (node (ref "CN16") (pin "3") (pinfunction "3_3") (pintype "unspecified"))
      (node (ref "R6") (pin "2") (pinfunction "2_2") (pintype "input"))
      (node (ref "U2") (pin "9") (pinfunction "SC2_9") (pintype "unspecified"))
    )
    (net (code "45") (name "Net-(U2-SC3)") (class "Default")
      (node (ref "CN17") (pin "3") (pinfunction "3_3") (pintype "unspecified"))
      (node (ref "R8") (pin "2") (pinfunction "2_2") (pintype "input"))
      (node (ref "U2") (pin "11") (pinfunction "SC3_11") (pintype "unspecified"))
    )
    (net (code "46") (name "Net-(U2-SC4)") (class "Default")
      (node (ref "CN18") (pin "3") (pinfunction "3_3") (pintype "unspecified"))
      (node (ref "R15") (pin "1") (pinfunction "1_1") (pintype "input"))
      (node (ref "U2") (pin "14") (pinfunction "SC4_14") (pintype "unspecified"))
    )
    (net (code "47") (name "Net-(U2-SC5)") (class "Default")
      (node (ref "CN19") (pin "3") (pinfunction "3_3") (pintype "unspecified"))
      (node (ref "R13") (pin "1") (pinfunction "1_1") (pintype "input"))
      (node (ref "U2") (pin "16") (pinfunction "SC5_16") (pintype "unspecified"))
    )
    (net (code "48") (name "Net-(U2-SC6)") (class "Default")
      (node (ref "CN20") (pin "3") (pinfunction "3_3") (pintype "unspecified"))
      (node (ref "R11") (pin "1") (pinfunction "1_1") (pintype "input"))
      (node (ref "U2") (pin "18") (pinfunction "SC6_18") (pintype "unspecified"))
    )
    (net (code "49") (name "Net-(U2-SC7)") (class "Default")
      (node (ref "CN21") (pin "3") (pinfunction "3_3") (pintype "unspecified"))
      (node (ref "R9") (pin "1") (pinfunction "1_1") (pintype "input"))
      (node (ref "U2") (pin "20") (pinfunction "SC7_20") (pintype "unspecified"))
    )
    (net (code "50") (name "Net-(U2-SD0)") (class "Default")
      (node (ref "CN14") (pin "4") (pinfunction "4_4") (pintype "unspecified"))
      (node (ref "R1") (pin "2") (pinfunction "2_2") (pintype "input"))
      (node (ref "U2") (pin "4") (pinfunction "SD0_4") (pintype "unspecified"))
    )
    (net (code "51") (name "Net-(U2-SD1)") (class "Default")
      (node (ref "CN15") (pin "4") (pinfunction "4_4") (pintype "unspecified"))
      (node (ref "R3") (pin "2") (pinfunction "2_2") (pintype "input"))
      (node (ref "U2") (pin "6") (pinfunction "SD1_6") (pintype "unspecified"))
    )
    (net (code "52") (name "Net-(U2-SD2)") (class "Default")
      (node (ref "CN16") (pin "4") (pinfunction "4_4") (pintype "unspecified"))
      (node (ref "R5") (pin "2") (pinfunction "2_2") (pintype "input"))
      (node (ref "U2") (pin "8") (pinfunction "SD2_8") (pintype "unspecified"))
    )
    (net (code "53") (name "Net-(U2-SD3)") (class "Default")
      (node (ref "CN17") (pin "4") (pinfunction "4_4") (pintype "unspecified"))
      (node (ref "R7") (pin "2") (pinfunction "2_2") (pintype "input"))
      (node (ref "U2") (pin "10") (pinfunction "SD3_10") (pintype "unspecified"))
    )
    (net (code "54") (name "Net-(U2-SD4)") (class "Default")
      (node (ref "CN18") (pin "4") (pinfunction "4_4") (pintype "unspecified"))
      (node (ref "R16") (pin "1") (pinfunction "1_1") (pintype "input"))
      (node (ref "U2") (pin "13") (pinfunction "SD4_13") (pintype "unspecified"))
    )
    (net (code "55") (name "Net-(U2-SD5)") (class "Default")
      (node (ref "CN19") (pin "4") (pinfunction "4_4") (pintype "unspecified"))
      (node (ref "R14") (pin "1") (pinfunction "1_1") (pintype "input"))
      (node (ref "U2") (pin "15") (pinfunction "SD5_15") (pintype "unspecified"))
    )
    (net (code "56") (name "Net-(U2-SD6)") (class "Default")
      (node (ref "CN20") (pin "4") (pinfunction "4_4") (pintype "unspecified"))
      (node (ref "R12") (pin "1") (pinfunction "1_1") (pintype "input"))
      (node (ref "U2") (pin "17") (pinfunction "SD6_17") (pintype "unspecified"))
    )
    (net (code "57") (name "Net-(U2-SD7)") (class "Default")
      (node (ref "CN21") (pin "4") (pinfunction "4_4") (pintype "unspecified"))
      (node (ref "R10") (pin "1") (pinfunction "1_1") (pintype "input"))
      (node (ref "U2") (pin "19") (pinfunction "SD7_19") (pintype "unspecified"))
    )
    (net (code "58") (name "ON_OFF") (class "Default")
      (node (ref "H18") (pin "4") (pinfunction "4_4") (pintype "unspecified"))
      (node (ref "U48") (pin "1") (pinfunction "1_1") (pintype "input"))
    )
    (net (code "59") (name "OUT1A") (class "Default")
      (node (ref "CN53") (pin "3") (pinfunction "3_3") (pintype "unspecified"))
      (node (ref "U1") (pin "9") (pinfunction "OUT1A/RX2_9") (pintype "unspecified"))
      (node (ref "U44") (pin "9") (pinfunction "9_9") (pintype "unspecified"))
    )
    (net (code "60") (name "OUT1C") (class "Default")
      (node (ref "U1") (pin "11") (pinfunction "OUT1C_11") (pintype "unspecified"))
      (node (ref "U44") (pin "11") (pinfunction "11_11") (pintype "unspecified"))
      (node (ref "U8") (pin "6") (pinfunction "6_6") (pintype "unspecified"))
    )
    (net (code "61") (name "OUT1D") (class "Default")
      (node (ref "CN52") (pin "3") (pinfunction "3_3") (pintype "unspecified"))
      (node (ref "U1") (pin "8") (pinfunction "OUT1D_8") (pintype "unspecified"))
      (node (ref "U44") (pin "8") (pinfunction "8_8") (pintype "unspecified"))
    )
    (net (code "62") (name "OUT2") (class "Default")
      (node (ref "Q19") (pin "2") (pinfunction "S_2") (pintype "unspecified"))
      (node (ref "R41") (pin "1") (pinfunction "1_1") (pintype "input"))
      (node (ref "U1") (pin "4") (pinfunction "OUT2_4") (pintype "unspecified"))
      (node (ref "U44") (pin "4") (pinfunction "4_4") (pintype "unspecified"))
    )
    (net (code "63") (name "PROGRAM") (class "Default")
      (node (ref "H18") (pin "2") (pinfunction "2_2") (pintype "unspecified"))
      (node (ref "U48") (pin "2") (pinfunction "2_2") (pintype "input"))
    )
    (net (code "64") (name "RX1") (class "Default")
      (node (ref "Q21") (pin "2") (pinfunction "S_2") (pintype "unspecified"))
      (node (ref "R45") (pin "1") (pinfunction "1_1") (pintype "input"))
      (node (ref "U1") (pin "2") (pinfunction "CRX2/CS1/RX1_2") (pintype "unspecified"))
      (node (ref "U44") (pin "2") (pinfunction "2_2") (pintype "unspecified"))
    )
    (net (code "65") (name "RX4") (class "Default")
      (node (ref "U1") (pin "38") (pinfunction "RX4/A2_38") (pintype "unspecified"))
      (node (ref "U43") (pin "11") (pinfunction "11_11") (pintype "unspecified"))
      (node (ref "U6") (pin "3") (pinfunction "3_3") (pintype "unspecified"))
    )
    (net (code "66") (name "RX5") (class "Default")
      (node (ref "CN13") (pin "3") (pinfunction "3_3") (pintype "unspecified"))
      (node (ref "U1") (pin "43") (pinfunction "RX5/A7_43") (pintype "unspecified"))
      (node (ref "U43") (pin "6") (pinfunction "6_6") (pintype "unspecified"))
    )
    (net (code "67") (name "RX7") (class "Default")
      (node (ref "U1") (pin "20") (pinfunction "RX7_20") (pintype "unspecified"))
      (node (ref "U44") (pin "20") (pinfunction "20_20") (pintype "unspecified"))
      (node (ref "U5") (pin "3") (pinfunction "3_3") (pintype "unspecified"))
    )
    (net (code "68") (name "SCK") (class "Default")
      (node (ref "U1") (pin "35") (pinfunction "SCK_35") (pintype "unspecified"))
      (node (ref "U4") (pin "5") (pinfunction "5_5") (pintype "unspecified"))
      (node (ref "U43") (pin "14") (pinfunction "14_14") (pintype "unspecified"))
      (node (ref "U8") (pin "5") (pinfunction "5_5") (pintype "unspecified"))
    )
    (net (code "69") (name "SCL") (class "Default")
      (node (ref "CN11") (pin "3") (pinfunction "3_3") (pintype "unspecified"))
      (node (ref "CN12") (pin "3") (pinfunction "3_3") (pintype "unspecified"))
      (node (ref "R17") (pin "1") (pinfunction "1_1") (pintype "input"))
      (node (ref "U1") (pin "41") (pinfunction "A5_41") (pintype "unspecified"))
      (node (ref "U2") (pin "22") (pinfunction "SCL_22") (pintype "unspecified"))
      (node (ref "U43") (pin "8") (pinfunction "8_8") (pintype "unspecified"))
    )
    (net (code "70") (name "SDA") (class "Default")
      (node (ref "CN11") (pin "4") (pinfunction "4_4") (pintype "unspecified"))
      (node (ref "CN12") (pin "4") (pinfunction "4_4") (pintype "unspecified"))
      (node (ref "R18") (pin "1") (pinfunction "1_1") (pintype "input"))
      (node (ref "U1") (pin "40") (pinfunction "A4_40") (pintype "unspecified"))
      (node (ref "U2") (pin "23") (pinfunction "SDA_23") (pintype "unspecified"))
      (node (ref "U43") (pin "9") (pinfunction "9_9") (pintype "unspecified"))
    )
    (net (code "71") (name "TRIG0") (class "Default")
      (node (ref "Q1") (pin "2") (pinfunction "S_2") (pintype "unspecified"))
      (node (ref "R20") (pin "2") (pinfunction "2_2") (pintype "input"))
      (node (ref "U1") (pin "24") (pinfunction "OUT1B_24") (pintype "unspecified"))
      (node (ref "U44") (pin "24") (pinfunction "24_24") (pintype "unspecified"))
    )
    (net (code "72") (name "TRIG1") (class "Default")
      (node (ref "Q3") (pin "2") (pinfunction "S_2") (pintype "unspecified"))
      (node (ref "R24") (pin "2") (pinfunction "2_2") (pintype "input"))
      (node (ref "U1") (pin "26") (pinfunction "RX8_26") (pintype "unspecified"))
      (node (ref "U43") (pin "23") (pinfunction "23_23") (pintype "unspecified"))
    )
    (net (code "73") (name "TRIG2") (class "Default")
      (node (ref "Q5") (pin "2") (pinfunction "S_2") (pintype "unspecified"))
      (node (ref "R28") (pin "2") (pinfunction "2_2") (pintype "input"))
      (node (ref "U1") (pin "28") (pinfunction "CS_28") (pintype "unspecified"))
      (node (ref "U43") (pin "21") (pinfunction "21_21") (pintype "unspecified"))
    )
    (net (code "74") (name "TRIG3") (class "Default")
      (node (ref "Q7") (pin "2") (pinfunction "S_2") (pintype "unspecified"))
      (node (ref "R32") (pin "2") (pinfunction "2_2") (pintype "input"))
      (node (ref "U1") (pin "36") (pinfunction "TX3/A0_36") (pintype "unspecified"))
      (node (ref "U43") (pin "13") (pinfunction "13_13") (pintype "unspecified"))
    )
    (net (code "75") (name "TX1") (class "Default")
      (node (ref "Q20") (pin "2") (pinfunction "S_2") (pintype "unspecified"))
      (node (ref "R43") (pin "1") (pinfunction "1_1") (pintype "input"))
      (node (ref "U1") (pin "3") (pinfunction "CTX2/MISO1/TX1_3") (pintype "unspecified"))
      (node (ref "U44") (pin "3") (pinfunction "3_3") (pintype "unspecified"))
    )
    (net (code "76") (name "TX4") (class "Default")
      (node (ref "U1") (pin "39") (pinfunction "TX4/A3_39") (pintype "unspecified"))
      (node (ref "U43") (pin "10") (pinfunction "10_10") (pintype "unspecified"))
      (node (ref "U6") (pin "4") (pinfunction "4_4") (pintype "unspecified"))
    )
    (net (code "77") (name "TX5") (class "Default")
      (node (ref "CN13") (pin "4") (pinfunction "4_4") (pintype "unspecified"))
      (node (ref "U1") (pin "42") (pinfunction "TX5/A6_42") (pintype "unspecified"))
      (node (ref "U43") (pin "7") (pinfunction "7_7") (pintype "unspecified"))
    )
    (net (code "78") (name "TX7") (class "Default")
      (node (ref "U1") (pin "21") (pinfunction "TX7_21") (pintype "unspecified"))
      (node (ref "U44") (pin "21") (pinfunction "21_21") (pintype "unspecified"))
      (node (ref "U5") (pin "4") (pinfunction "4_4") (pintype "unspecified"))
    )
    (net (code "79") (name "unconnected-(U48-Pad4)") (class "Default")
      (node (ref "U48") (pin "4") (pinfunction "4_4") (pintype "input+no_connect"))
    )
    (net (code "80") (name "unconnected-(U48-Pad5)") (class "Default")
      (node (ref "U48") (pin "5") (pinfunction "5_5") (pintype "input+no_connect"))
    )
  )
)
